# Audio_Spektrum_Analyser.net
KiCad netlist of a schematic drawn in EAGLE
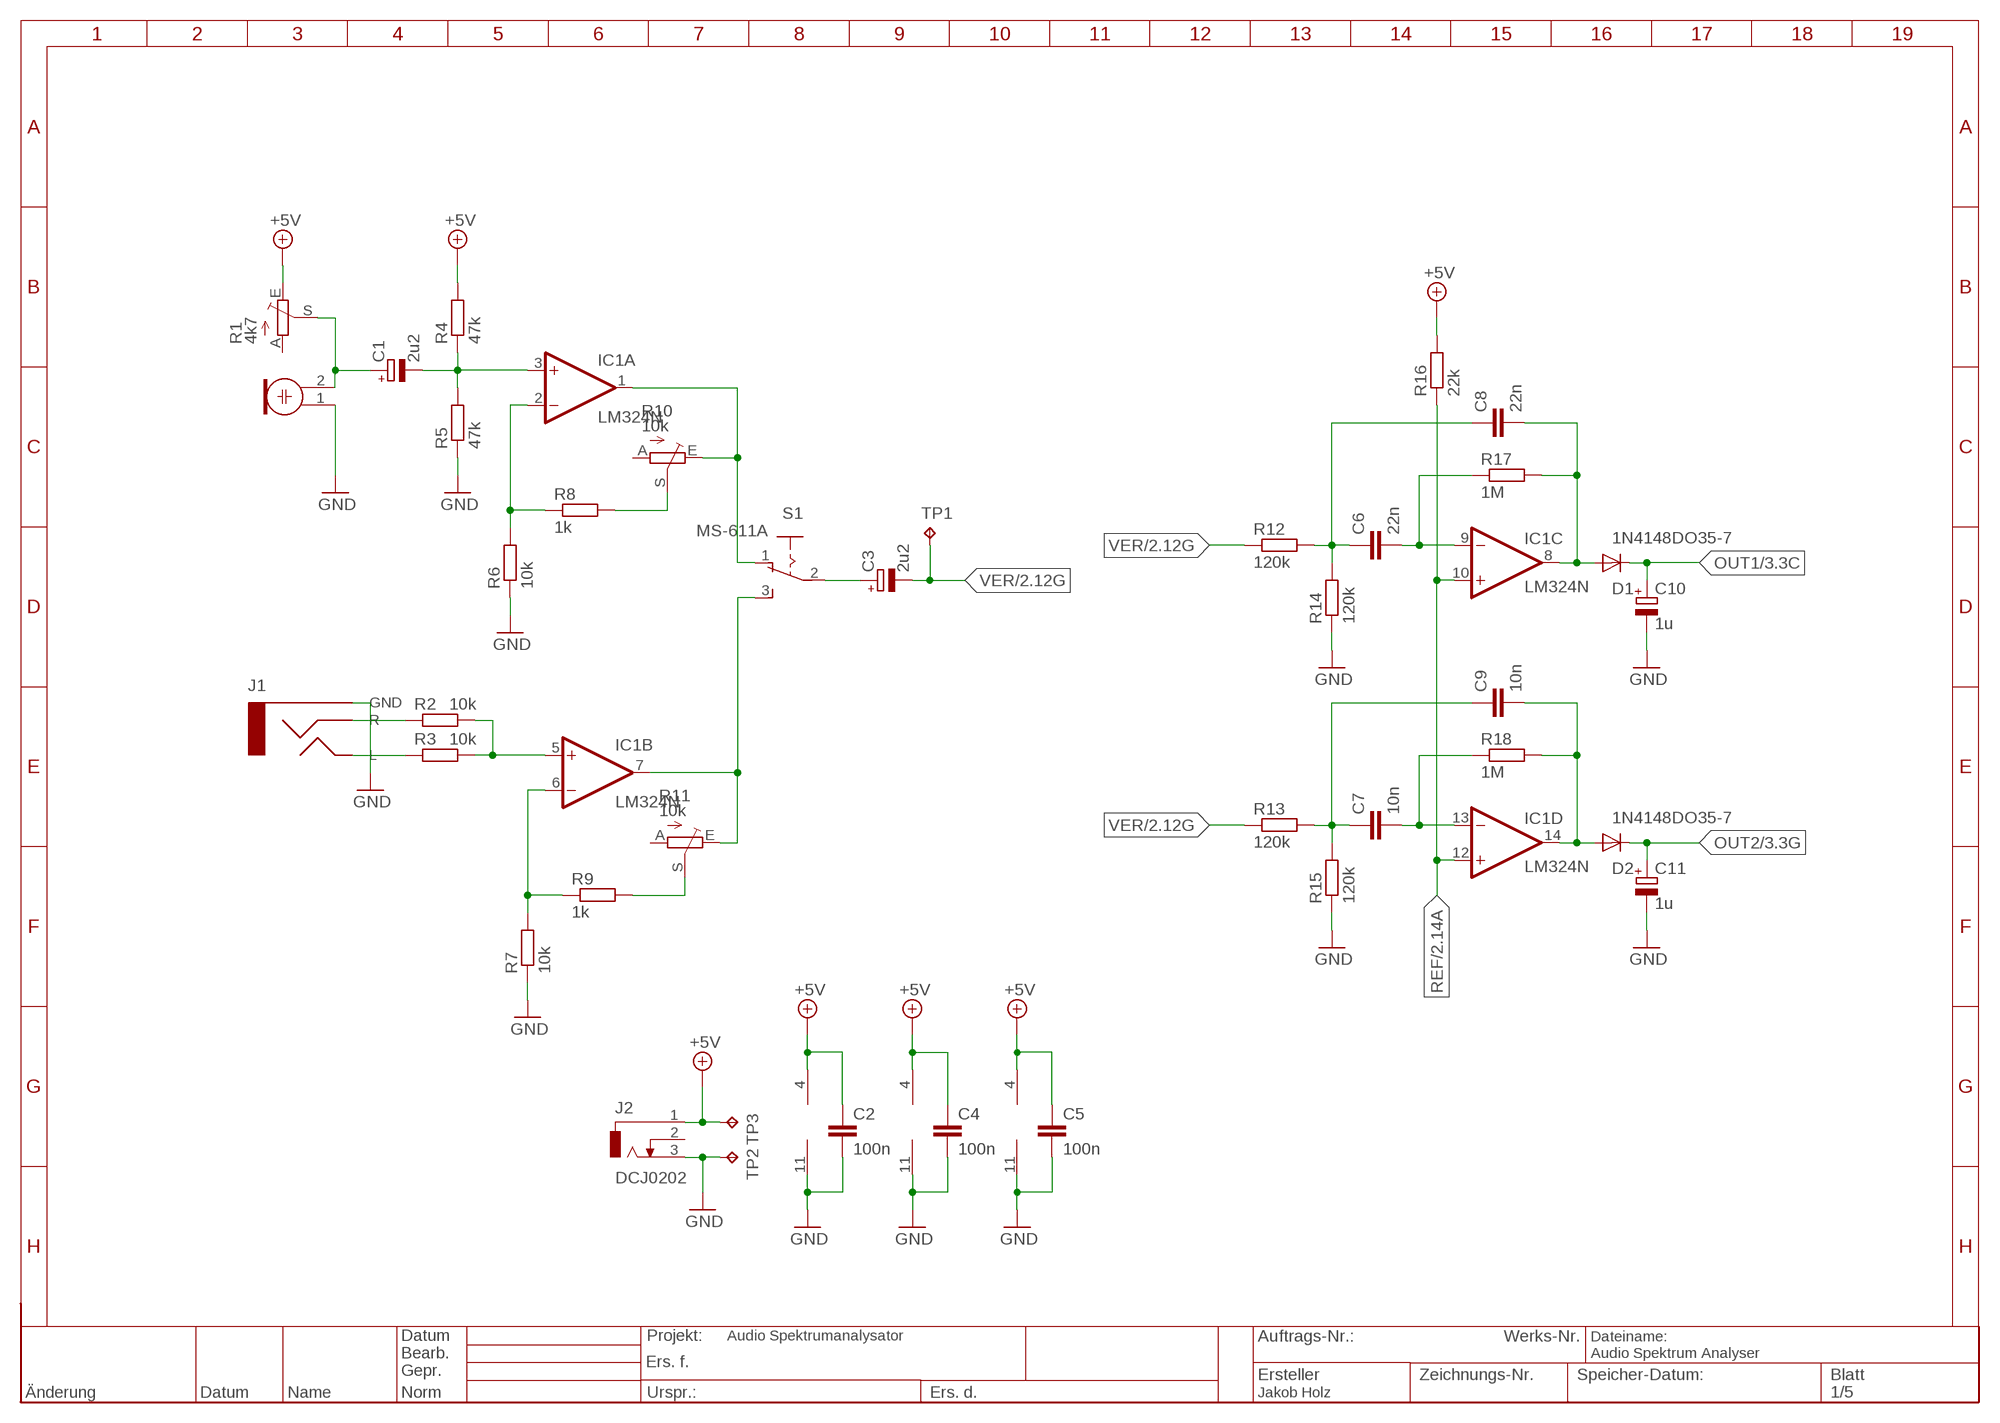
[diagram p0: schematic, sheet 1]
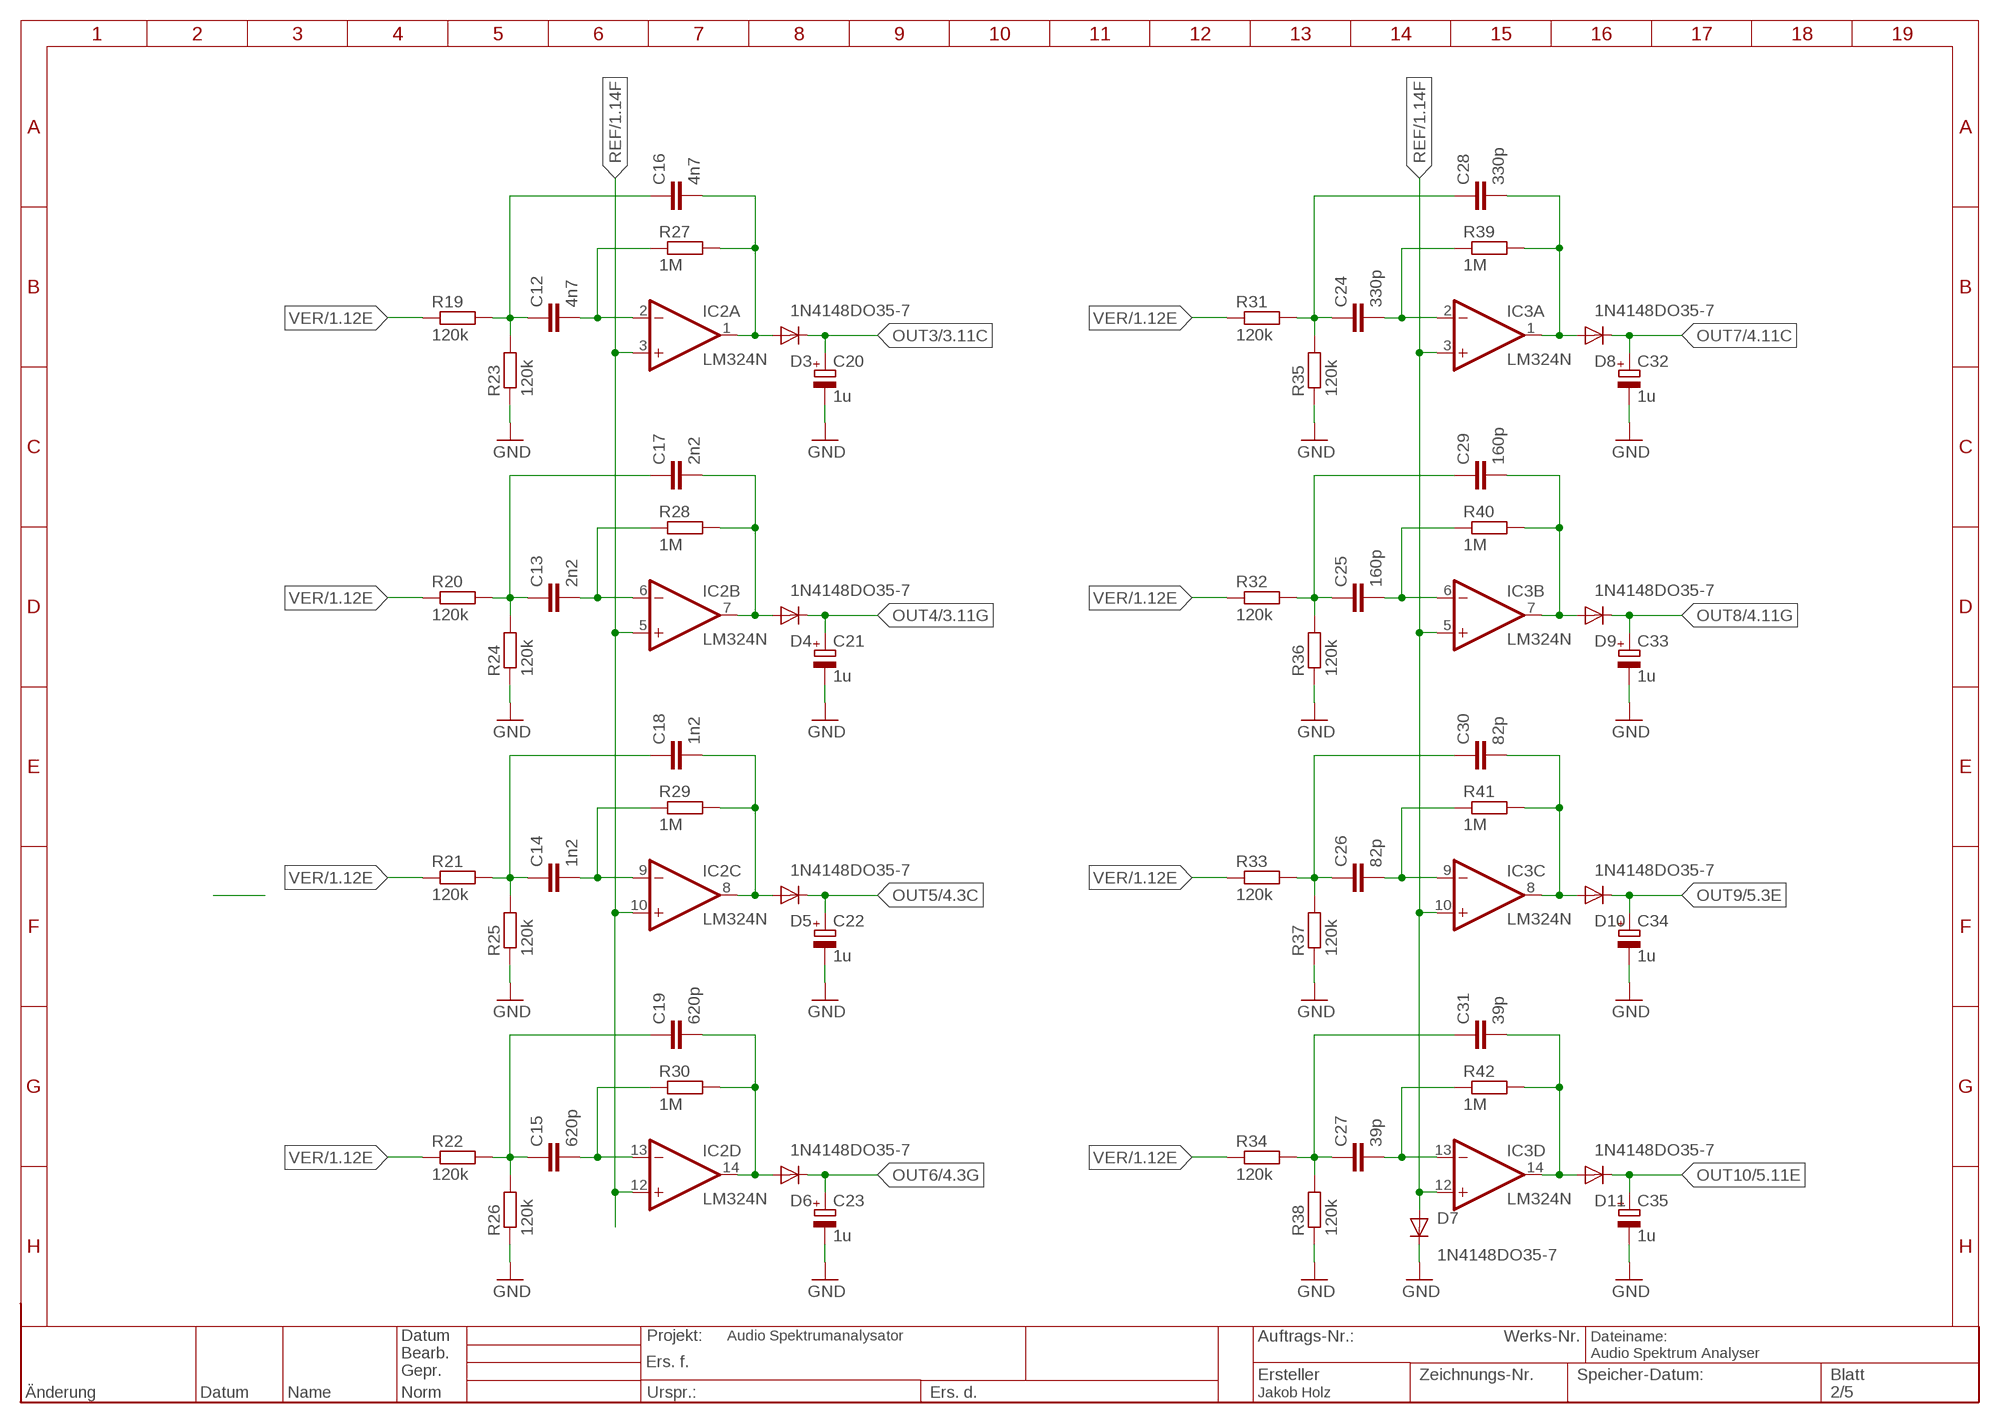
[diagram p1: schematic, sheet 2]
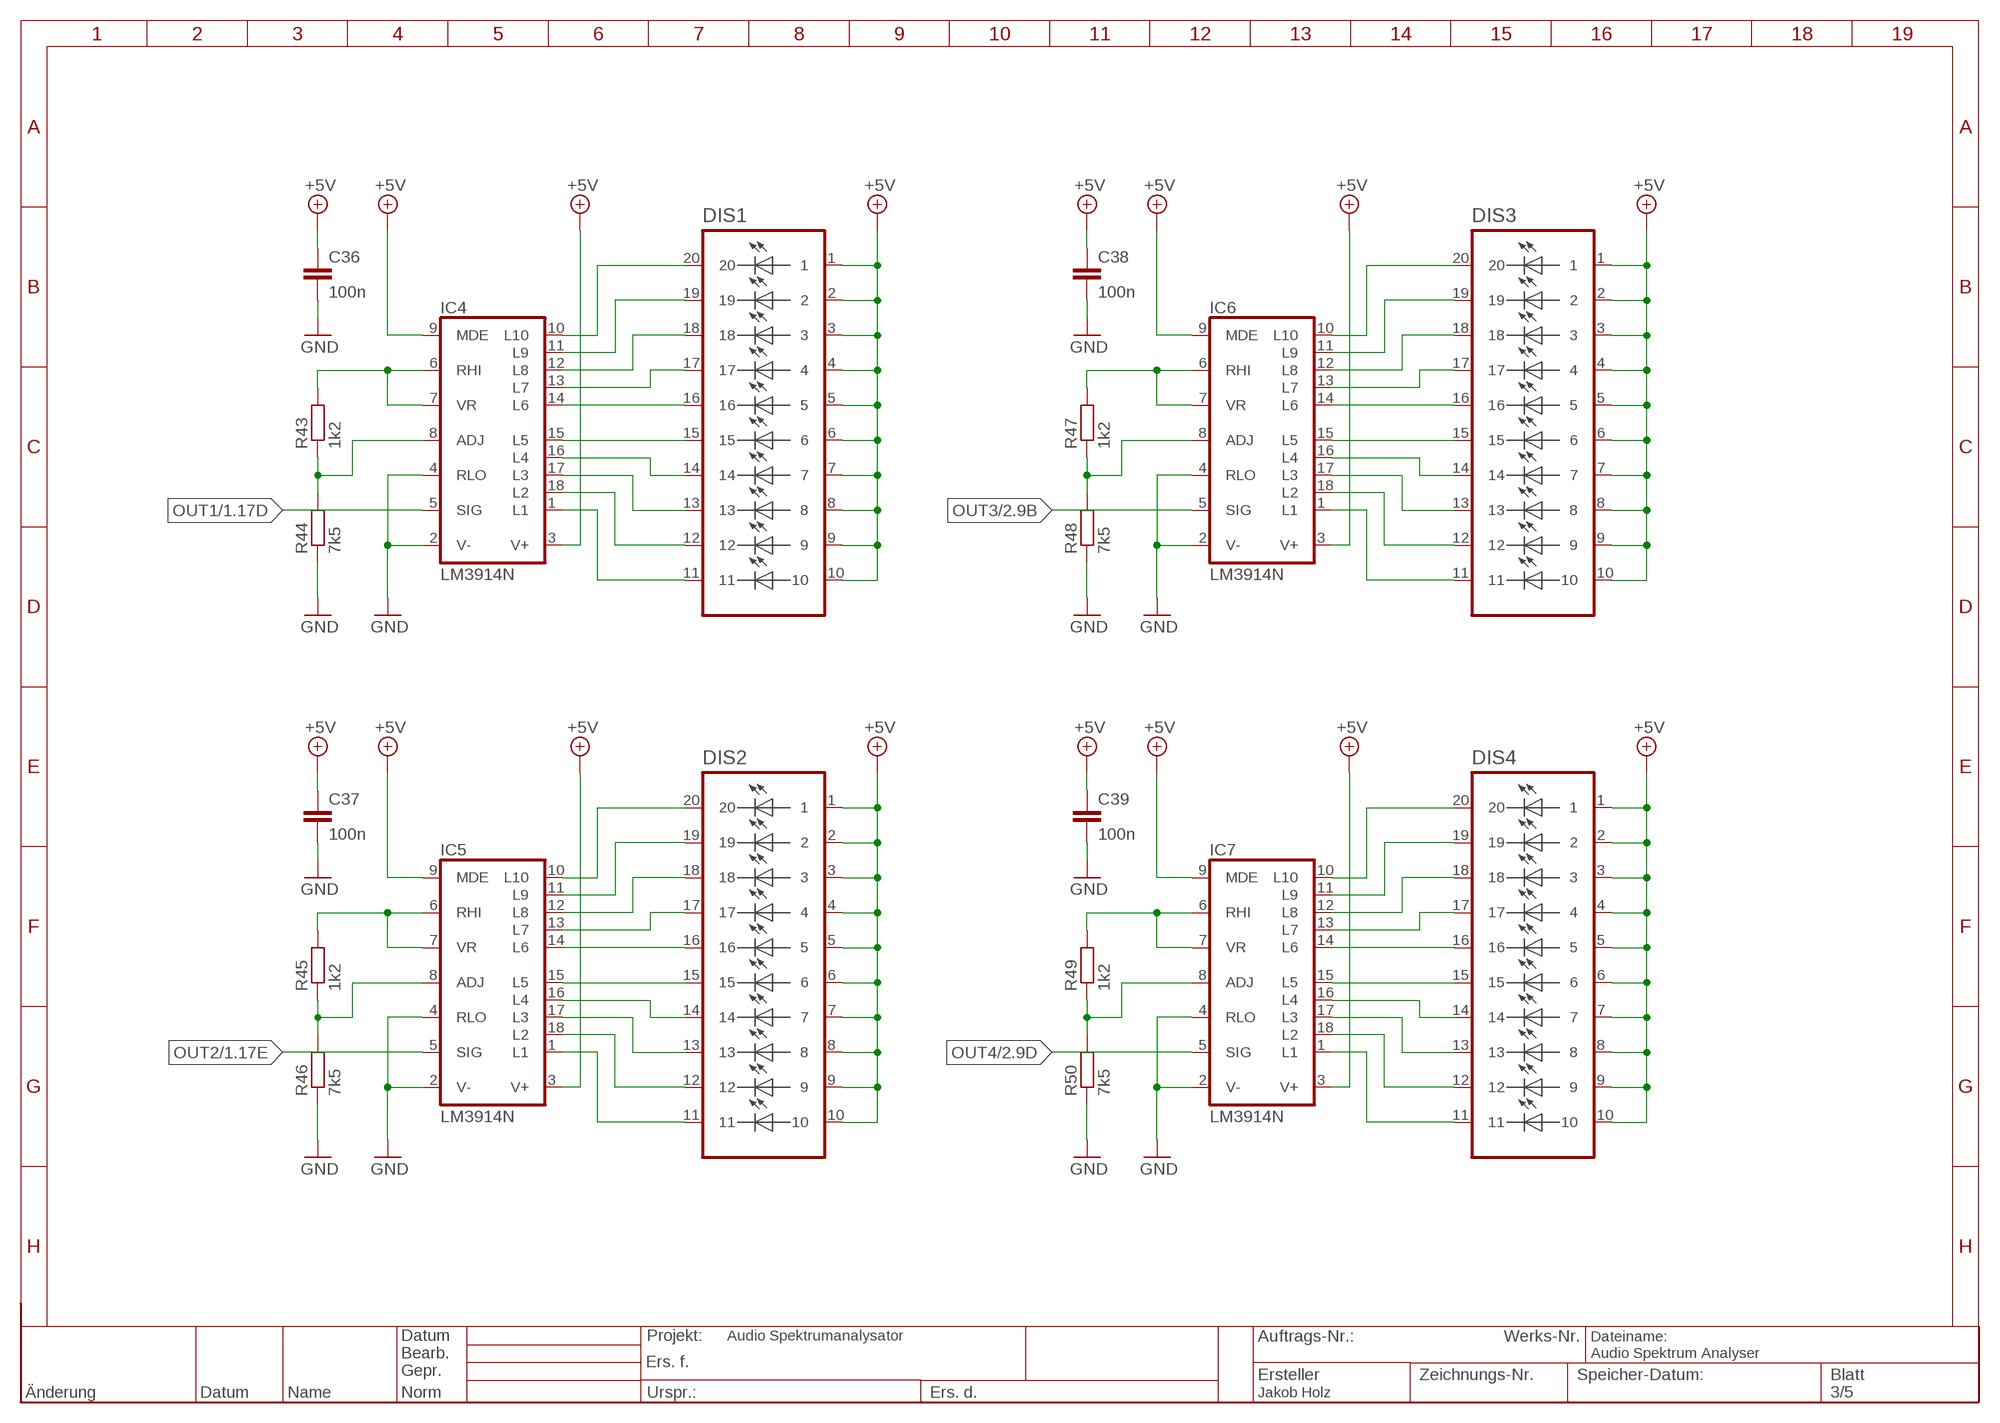
[diagram p2: schematic, sheet 3]
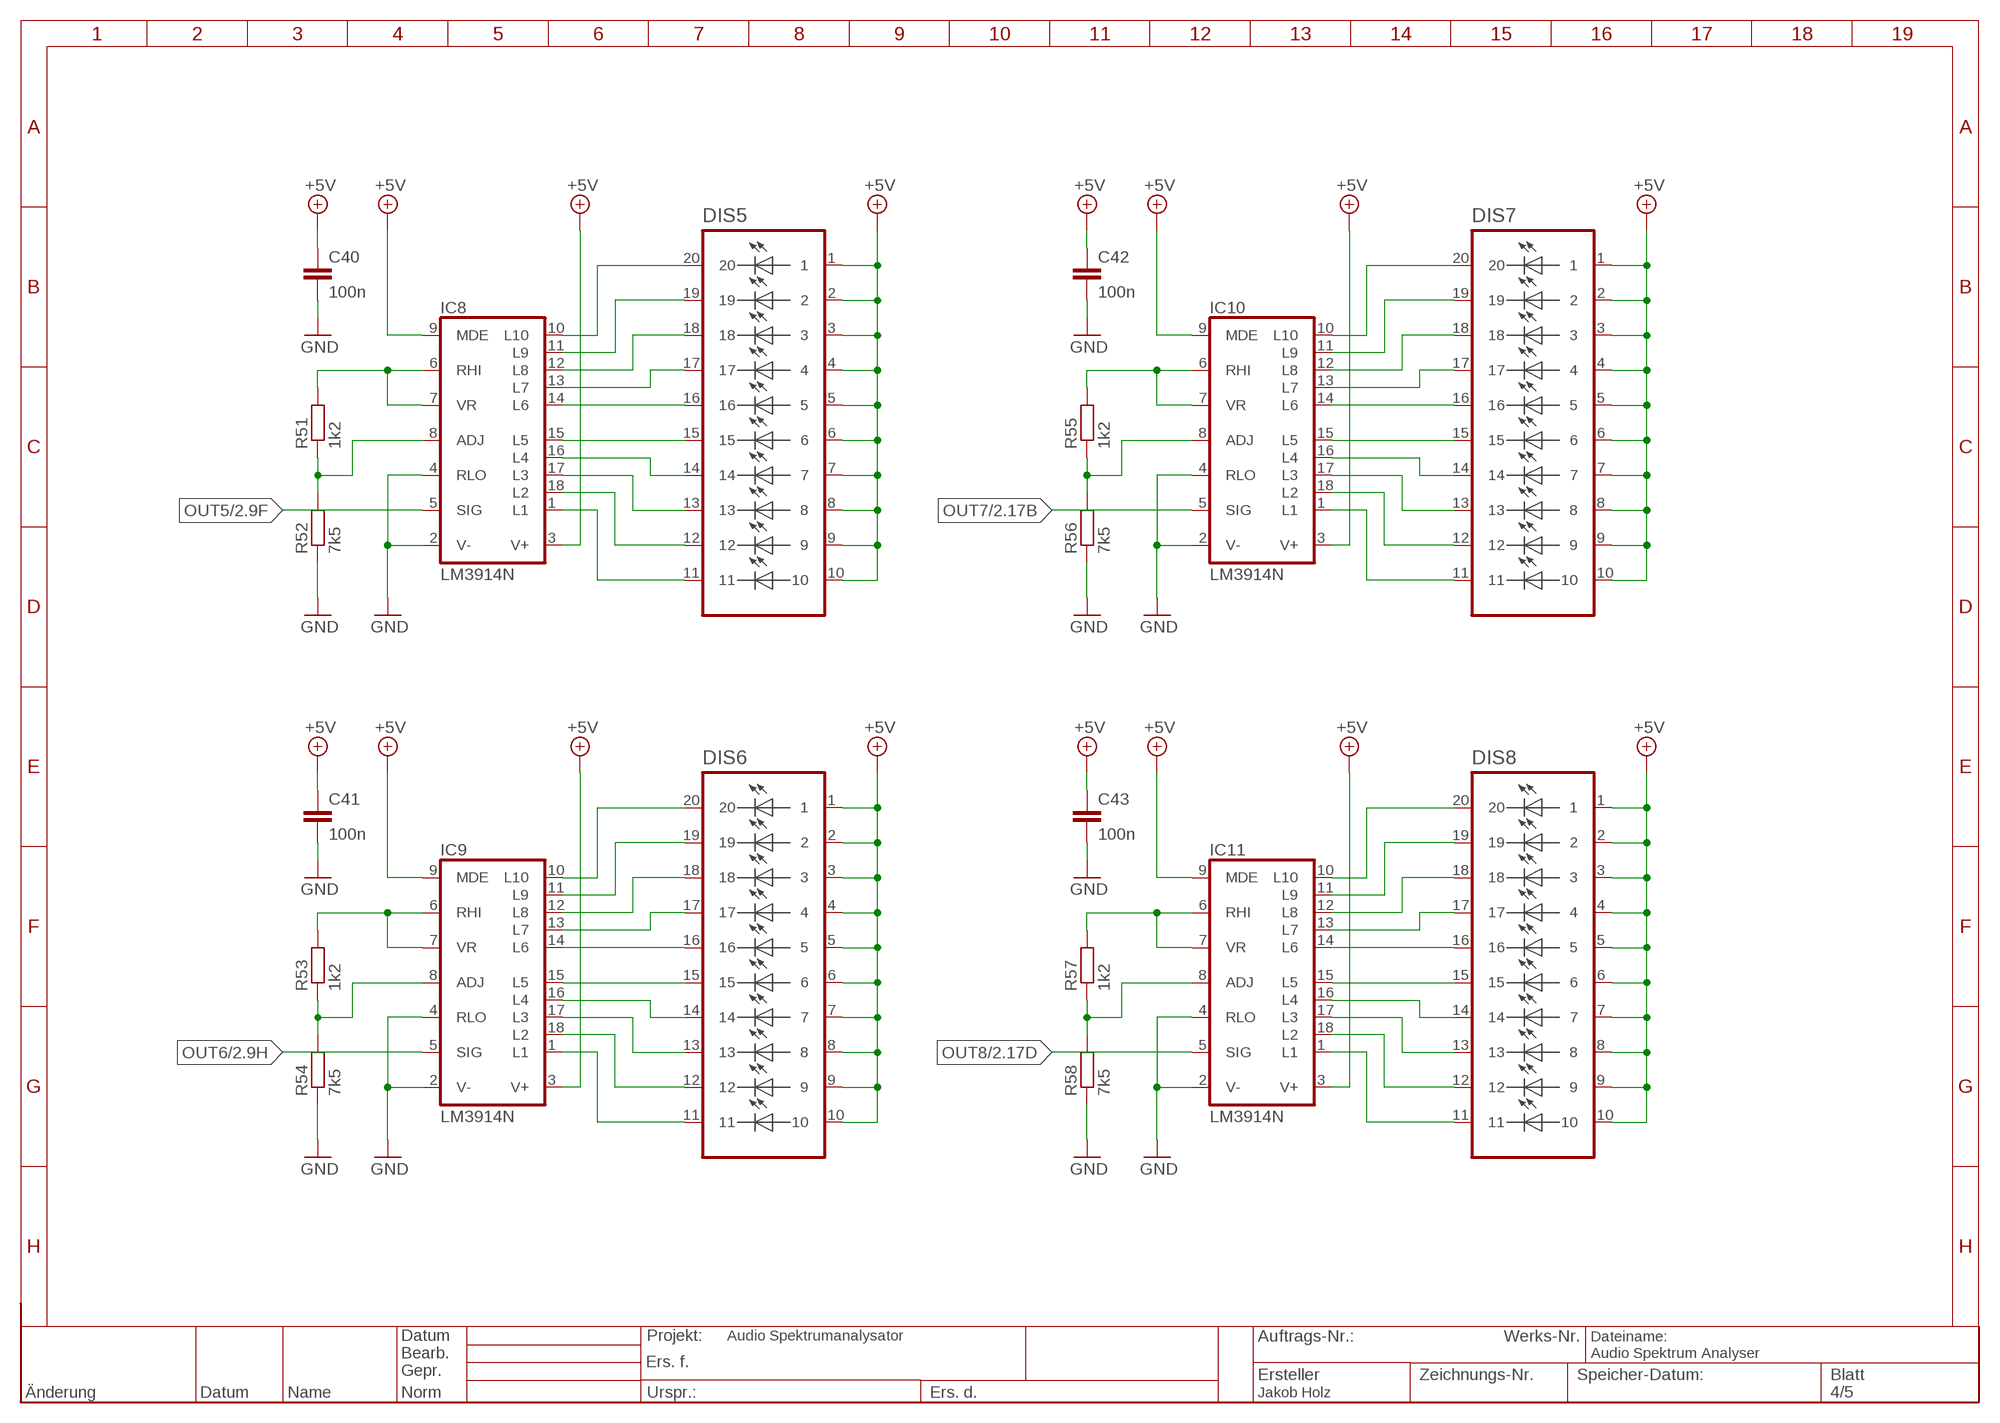
[diagram p3: schematic, sheet 4]
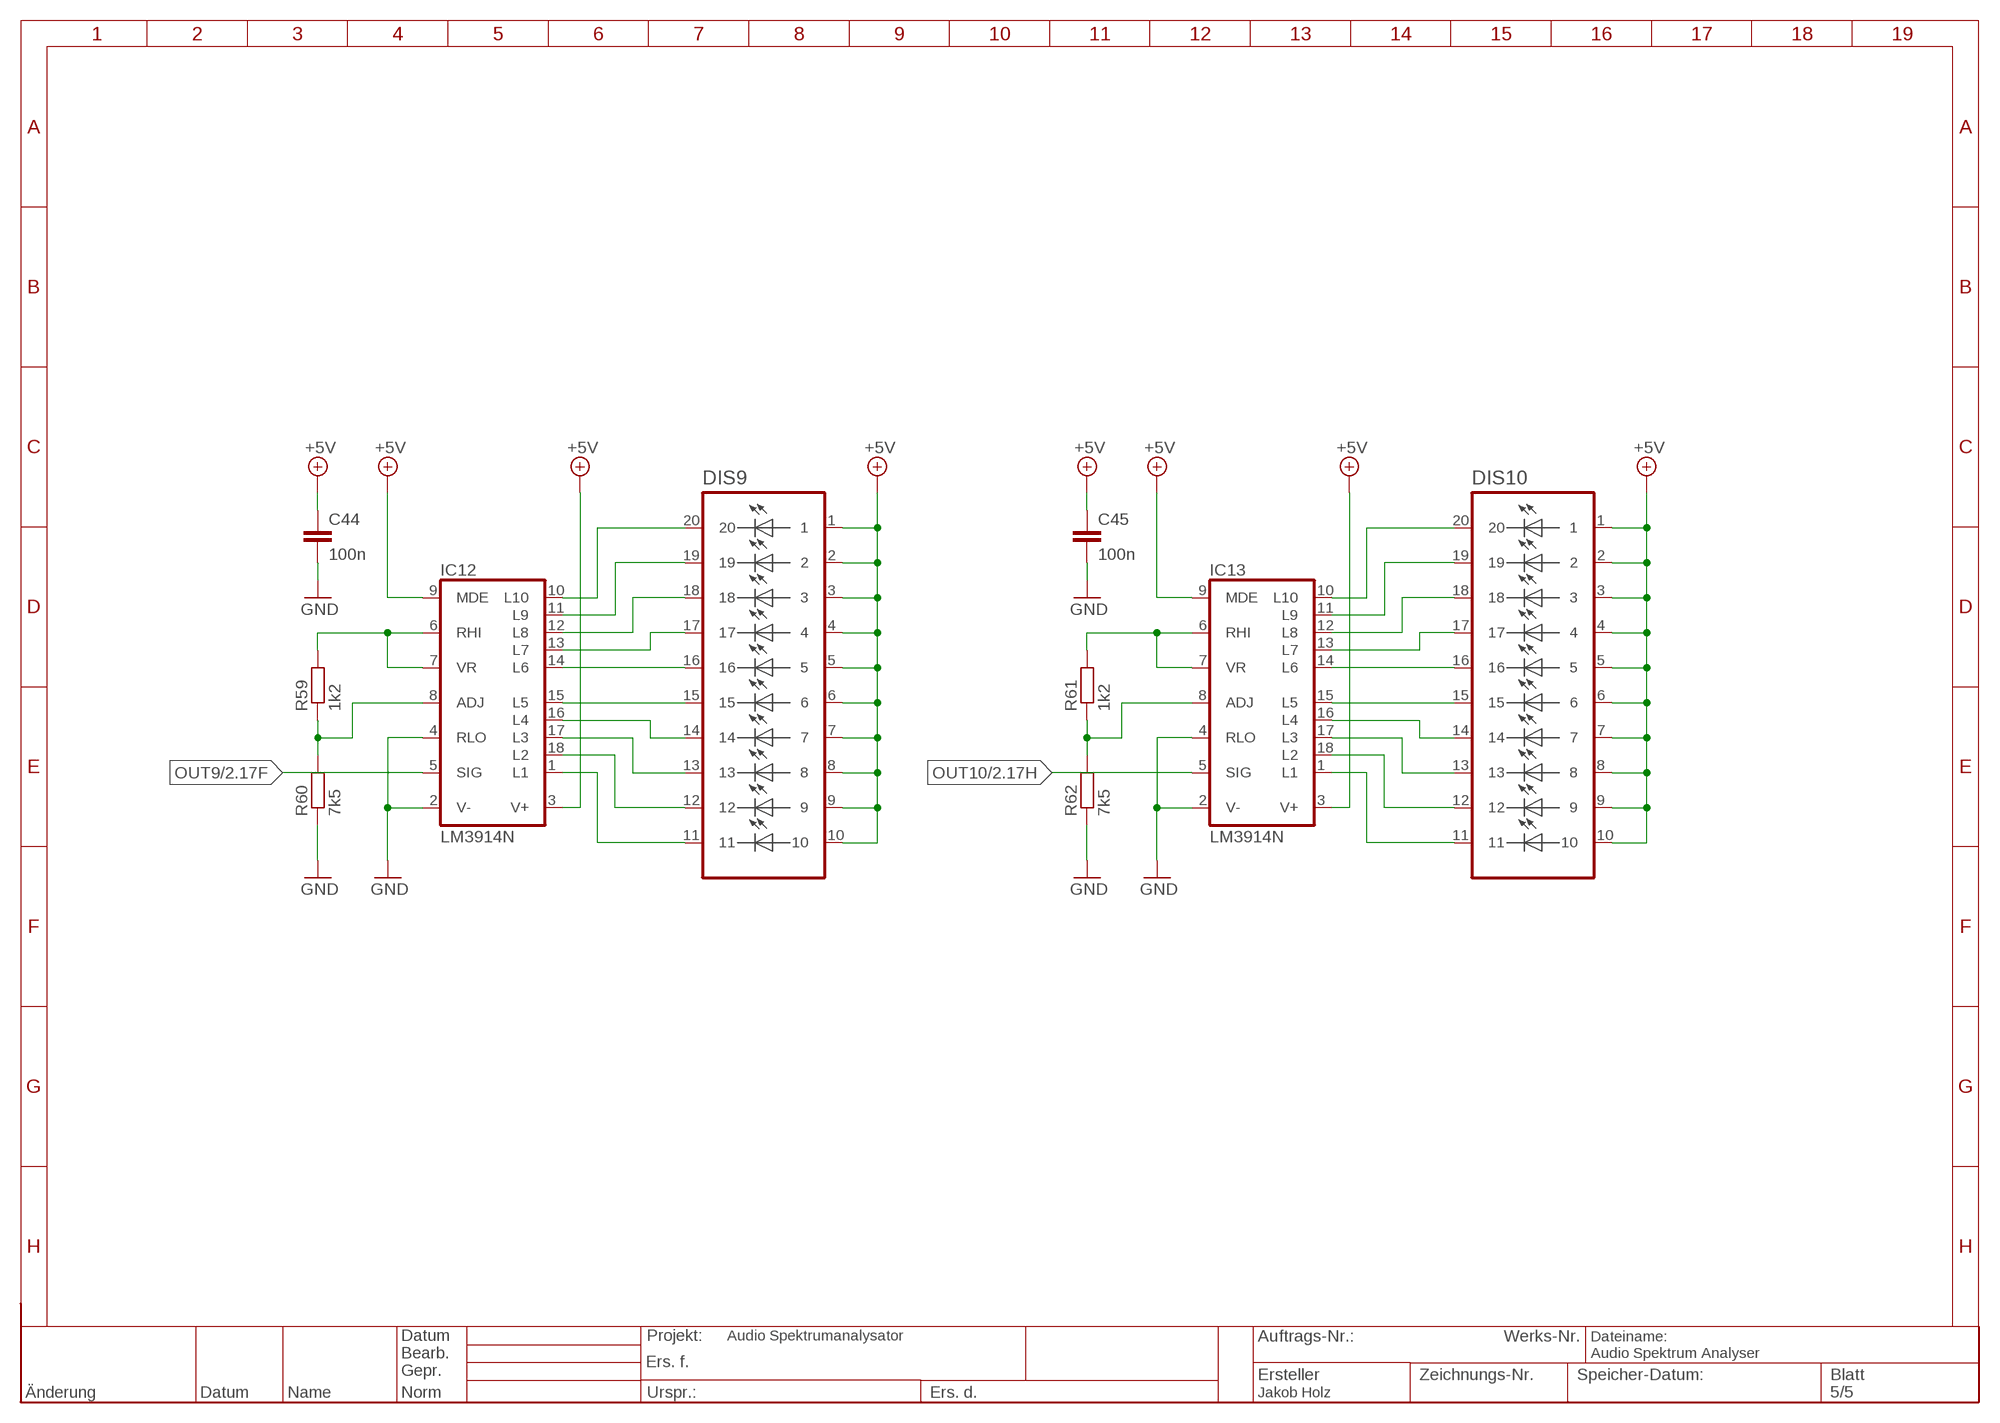
[diagram p4: schematic, sheet 5]

(export (version "E")
  (design (tool "Eeschema 10.0.6"))
  (components
    (comp (ref "C44")
      (value "100n")
      (footprint "eagle-import:C050-024X044")
      (libsource (lib "eagle-import") (part "C-EU050-024X044"))
    )
    (comp (ref "C45")
      (value "100n")
      (footprint "eagle-import:C050-024X044")
      (libsource (lib "eagle-import") (part "C-EU050-024X044"))
    )
    (comp (ref "DIS9")
      (value "SHB10R")
      (footprint "eagle-import:SHB10R")
      (libsource (lib "eagle-import") (part "SHB10R"))
    )
    (comp (ref "DIS10")
      (value "SHB10R")
      (footprint "eagle-import:SHB10R")
      (libsource (lib "eagle-import") (part "SHB10R"))
    )
    (comp (ref "IC12")
      (value "LM3914N")
      (footprint "eagle-import:DIL18")
      (libsource (lib "eagle-import") (part "LM3914N"))
    )
    (comp (ref "IC13")
      (value "LM3914N")
      (footprint "eagle-import:DIL18")
      (libsource (lib "eagle-import") (part "LM3914N"))
    )
    (comp (ref "R59")
      (value "1k2")
      (footprint "eagle-import:0207_7")
      (libsource (lib "eagle-import") (part "resistor_348_R-EU_0207/7"))
    )
    (comp (ref "R60")
      (value "7k5")
      (footprint "eagle-import:0207_7")
      (libsource (lib "eagle-import") (part "resistor_348_R-EU_0207/7"))
    )
    (comp (ref "R61")
      (value "1k2")
      (footprint "eagle-import:0207_7")
      (libsource (lib "eagle-import") (part "resistor_348_R-EU_0207/7"))
    )
    (comp (ref "R62")
      (value "7k5")
      (footprint "eagle-import:0207_7")
      (libsource (lib "eagle-import") (part "resistor_348_R-EU_0207/7"))
    )
    (comp (ref "C1")
      (value "2u2")
      (footprint "eagle-import:E2,5-5")
      (libsource (lib "eagle-import") (part "CPOL-EUE2.5-5"))
    )
    (comp (ref "C2")
      (value "100n")
      (footprint "eagle-import:C050-024X044")
      (libsource (lib "eagle-import") (part "C-EU050-024X044"))
    )
    (comp (ref "C3")
      (value "2u2")
      (footprint "eagle-import:E2,5-5")
      (libsource (lib "eagle-import") (part "CPOL-EUE2.5-5"))
    )
    (comp (ref "C4")
      (value "100n")
      (footprint "eagle-import:C050-024X044")
      (libsource (lib "eagle-import") (part "C-EU050-024X044"))
    )
    (comp (ref "C5")
      (value "100n")
      (footprint "eagle-import:C050-024X044")
      (libsource (lib "eagle-import") (part "C-EU050-024X044"))
    )
    (comp (ref "C6")
      (value "22n")
      (footprint "eagle-import:C025-024X044")
      (libsource (lib "eagle-import") (part "C-EU025-024X044"))
    )
    (comp (ref "C7")
      (value "10n")
      (footprint "eagle-import:C025-024X044")
      (libsource (lib "eagle-import") (part "C-EU025-024X044"))
    )
    (comp (ref "C8")
      (value "22n")
      (footprint "eagle-import:C025-024X044")
      (libsource (lib "eagle-import") (part "C-EU025-024X044"))
    )
    (comp (ref "C9")
      (value "10n")
      (footprint "eagle-import:C025-024X044")
      (libsource (lib "eagle-import") (part "C-EU025-024X044"))
    )
    (comp (ref "C10")
      (value "1u")
      (footprint "eagle-import:E2,5-5")
      (libsource (lib "eagle-import") (part "CPOL-EUE2.5-5"))
    )
    (comp (ref "C11")
      (value "1u")
      (footprint "eagle-import:E2,5-5")
      (libsource (lib "eagle-import") (part "CPOL-EUE2.5-5"))
    )
    (comp (ref "D1")
      (value "1N4148DO35-7")
      (footprint "eagle-import:DO35-7")
      (libsource (lib "eagle-import") (part "1N4148DO35-7"))
    )
    (comp (ref "D2")
      (value "1N4148DO35-7")
      (footprint "eagle-import:DO35-7")
      (libsource (lib "eagle-import") (part "1N4148DO35-7"))
    )
    (comp (ref "IC1")
      (value "LM324N")
      (footprint "eagle-import:DIL14")
      (libsource (lib "eagle-import") (part "LM324N"))
    )
    (comp (ref "IC2")
      (value "LM324N")
      (footprint "eagle-import:DIL14")
      (libsource (lib "eagle-import") (part "LM324N"))
    )
    (comp (ref "IC3")
      (value "LM324N")
      (footprint "eagle-import:DIL14")
      (libsource (lib "eagle-import") (part "LM324N"))
    )
    (comp (ref "J1")
      (value "2.5MM-AUXPC")
      (footprint "eagle-import:2.5MM-AUX_PC")
      (libsource (lib "eagle-import") (part "2.5MM-AUXPC"))
    )
    (comp (ref "J2")
      (value "DCJ0202")
      (footprint "eagle-import:DCJ0202")
      (libsource (lib "eagle-import") (part "DCJ0202"))
    )
    (comp (ref "M1")
      (value "ELECTRET_MICROPHON-F6050AP")
      (footprint "eagle-import:F6050AP")
      (libsource (lib "eagle-import") (part "ELECTRET_MICROPHON-F6050AP"))
    )
    (comp (ref "R1")
      (value "4k7")
      (footprint "eagle-import:CA6V")
      (libsource (lib "eagle-import") (part "TRIM_EU-CA6V"))
    )
    (comp (ref "R2")
      (value "10k")
      (footprint "eagle-import:0207_7")
      (libsource (lib "eagle-import") (part "R-EU_0207/7"))
    )
    (comp (ref "R3")
      (value "10k")
      (footprint "eagle-import:0207_7")
      (libsource (lib "eagle-import") (part "R-EU_0207/7"))
    )
    (comp (ref "R4")
      (value "47k")
      (footprint "eagle-import:0207_7")
      (libsource (lib "eagle-import") (part "R-EU_0207/7"))
    )
    (comp (ref "R5")
      (value "47k")
      (footprint "eagle-import:0207_7")
      (libsource (lib "eagle-import") (part "R-EU_0207/7"))
    )
    (comp (ref "R6")
      (value "10k")
      (footprint "eagle-import:0207_7")
      (libsource (lib "eagle-import") (part "R-EU_0207/7"))
    )
    (comp (ref "R7")
      (value "10k")
      (footprint "eagle-import:0207_7")
      (libsource (lib "eagle-import") (part "resistor_348_R-EU_0207/7"))
    )
    (comp (ref "R8")
      (value "1k")
      (footprint "eagle-import:0207_7")
      (libsource (lib "eagle-import") (part "R-EU_0207/7"))
    )
    (comp (ref "R9")
      (value "1k")
      (footprint "eagle-import:0207_7")
      (libsource (lib "eagle-import") (part "resistor_348_R-EU_0207/7"))
    )
    (comp (ref "R10")
      (value "10k")
      (footprint "eagle-import:CA6V")
      (libsource (lib "eagle-import") (part "TRIM_EU-CA6V"))
    )
    (comp (ref "R11")
      (value "10k")
      (footprint "eagle-import:CA6V")
      (libsource (lib "eagle-import") (part "TRIM_EU-CA6V"))
    )
    (comp (ref "R12")
      (value "120k")
      (footprint "eagle-import:0207_7")
      (libsource (lib "eagle-import") (part "resistor_348_R-EU_0207/7"))
    )
    (comp (ref "R13")
      (value "120k")
      (footprint "eagle-import:0207_7")
      (libsource (lib "eagle-import") (part "resistor_348_R-EU_0207/7"))
    )
    (comp (ref "R14")
      (value "120k")
      (footprint "eagle-import:0207_7")
      (libsource (lib "eagle-import") (part "resistor_348_R-EU_0207/7"))
    )
    (comp (ref "R15")
      (value "120k")
      (footprint "eagle-import:0207_7")
      (libsource (lib "eagle-import") (part "resistor_348_R-EU_0207/7"))
    )
    (comp (ref "R16")
      (value "22k")
      (footprint "eagle-import:0207_7")
      (libsource (lib "eagle-import") (part "resistor_348_R-EU_0207/7"))
    )
    (comp (ref "R17")
      (value "1M")
      (footprint "eagle-import:0207_7")
      (libsource (lib "eagle-import") (part "resistor_348_R-EU_0207/7"))
    )
    (comp (ref "R18")
      (value "1M")
      (footprint "eagle-import:0207_7")
      (libsource (lib "eagle-import") (part "resistor_348_R-EU_0207/7"))
    )
    (comp (ref "S1")
      (value "MS-611A")
      (footprint "eagle-import:MS-611A")
      (libsource (lib "eagle-import") (part "MS-611A"))
    )
    (comp (ref "TP1")
      (value "TPPAD1-20")
      (footprint "eagle-import:P1-20")
      (libsource (lib "eagle-import") (part "TPPAD1-20"))
    )
    (comp (ref "TP2")
      (value "TPPAD1-20")
      (footprint "eagle-import:P1-20")
      (libsource (lib "eagle-import") (part "TPPAD1-20"))
    )
    (comp (ref "TP3")
      (value "TPPAD1-20")
      (footprint "eagle-import:P1-20")
      (libsource (lib "eagle-import") (part "TPPAD1-20"))
    )
    (comp (ref "C36")
      (value "100n")
      (footprint "eagle-import:C050-024X044")
      (libsource (lib "eagle-import") (part "C-EU050-024X044"))
    )
    (comp (ref "C37")
      (value "100n")
      (footprint "eagle-import:C050-024X044")
      (libsource (lib "eagle-import") (part "C-EU050-024X044"))
    )
    (comp (ref "C38")
      (value "100n")
      (footprint "eagle-import:C050-024X044")
      (libsource (lib "eagle-import") (part "C-EU050-024X044"))
    )
    (comp (ref "C39")
      (value "100n")
      (footprint "eagle-import:C050-024X044")
      (libsource (lib "eagle-import") (part "C-EU050-024X044"))
    )
    (comp (ref "DIS1")
      (value "SHB10R")
      (footprint "eagle-import:SHB10R")
      (libsource (lib "eagle-import") (part "SHB10R"))
    )
    (comp (ref "DIS2")
      (value "SHB10R")
      (footprint "eagle-import:SHB10R")
      (libsource (lib "eagle-import") (part "SHB10R"))
    )
    (comp (ref "DIS3")
      (value "SHB10R")
      (footprint "eagle-import:SHB10R")
      (libsource (lib "eagle-import") (part "SHB10R"))
    )
    (comp (ref "DIS4")
      (value "SHB10R")
      (footprint "eagle-import:SHB10R")
      (libsource (lib "eagle-import") (part "SHB10R"))
    )
    (comp (ref "IC4")
      (value "LM3914N")
      (footprint "eagle-import:DIL18")
      (libsource (lib "eagle-import") (part "LM3914N"))
    )
    (comp (ref "IC5")
      (value "LM3914N")
      (footprint "eagle-import:DIL18")
      (libsource (lib "eagle-import") (part "LM3914N"))
    )
    (comp (ref "IC6")
      (value "LM3914N")
      (footprint "eagle-import:DIL18")
      (libsource (lib "eagle-import") (part "LM3914N"))
    )
    (comp (ref "IC7")
      (value "LM3914N")
      (footprint "eagle-import:DIL18")
      (libsource (lib "eagle-import") (part "LM3914N"))
    )
    (comp (ref "R43")
      (value "1k2")
      (footprint "eagle-import:0207_7")
      (libsource (lib "eagle-import") (part "resistor_348_R-EU_0207/7"))
    )
    (comp (ref "R44")
      (value "7k5")
      (footprint "eagle-import:0207_7")
      (libsource (lib "eagle-import") (part "resistor_348_R-EU_0207/7"))
    )
    (comp (ref "R45")
      (value "1k2")
      (footprint "eagle-import:0207_7")
      (libsource (lib "eagle-import") (part "resistor_348_R-EU_0207/7"))
    )
    (comp (ref "R46")
      (value "7k5")
      (footprint "eagle-import:0207_7")
      (libsource (lib "eagle-import") (part "resistor_348_R-EU_0207/7"))
    )
    (comp (ref "R47")
      (value "1k2")
      (footprint "eagle-import:0207_7")
      (libsource (lib "eagle-import") (part "resistor_348_R-EU_0207/7"))
    )
    (comp (ref "R48")
      (value "7k5")
      (footprint "eagle-import:0207_7")
      (libsource (lib "eagle-import") (part "resistor_348_R-EU_0207/7"))
    )
    (comp (ref "R49")
      (value "1k2")
      (footprint "eagle-import:0207_7")
      (libsource (lib "eagle-import") (part "resistor_348_R-EU_0207/7"))
    )
    (comp (ref "R50")
      (value "7k5")
      (footprint "eagle-import:0207_7")
      (libsource (lib "eagle-import") (part "resistor_348_R-EU_0207/7"))
    )
    (comp (ref "C12")
      (value "4n7")
      (footprint "eagle-import:C025-024X044")
      (libsource (lib "eagle-import") (part "C-EU025-024X044"))
    )
    (comp (ref "C13")
      (value "2n2")
      (footprint "eagle-import:C025-024X044")
      (libsource (lib "eagle-import") (part "C-EU025-024X044"))
    )
    (comp (ref "C14")
      (value "1n2")
      (footprint "eagle-import:C025-024X044")
      (libsource (lib "eagle-import") (part "C-EU025-024X044"))
    )
    (comp (ref "C15")
      (value "620p")
      (footprint "eagle-import:C025-024X044")
      (libsource (lib "eagle-import") (part "C-EU025-024X044"))
    )
    (comp (ref "C16")
      (value "4n7")
      (footprint "eagle-import:C025-024X044")
      (libsource (lib "eagle-import") (part "C-EU025-024X044"))
    )
    (comp (ref "C17")
      (value "2n2")
      (footprint "eagle-import:C025-024X044")
      (libsource (lib "eagle-import") (part "C-EU025-024X044"))
    )
    (comp (ref "C18")
      (value "1n2")
      (footprint "eagle-import:C025-024X044")
      (libsource (lib "eagle-import") (part "C-EU025-024X044"))
    )
    (comp (ref "C19")
      (value "620p")
      (footprint "eagle-import:C025-024X044")
      (libsource (lib "eagle-import") (part "C-EU025-024X044"))
    )
    (comp (ref "C20")
      (value "1u")
      (footprint "eagle-import:E2,5-5")
      (libsource (lib "eagle-import") (part "CPOL-EUE2.5-5"))
    )
    (comp (ref "C21")
      (value "1u")
      (footprint "eagle-import:E2,5-5")
      (libsource (lib "eagle-import") (part "CPOL-EUE2.5-5"))
    )
    (comp (ref "C22")
      (value "1u")
      (footprint "eagle-import:E2,5-5")
      (libsource (lib "eagle-import") (part "CPOL-EUE2.5-5"))
    )
    (comp (ref "C23")
      (value "1u")
      (footprint "eagle-import:E2,5-5")
      (libsource (lib "eagle-import") (part "CPOL-EUE2.5-5"))
    )
    (comp (ref "C24")
      (value "330p")
      (footprint "eagle-import:C025-024X044")
      (libsource (lib "eagle-import") (part "C-EU025-024X044"))
    )
    (comp (ref "C25")
      (value "160p")
      (footprint "eagle-import:C025-024X044")
      (libsource (lib "eagle-import") (part "C-EU025-024X044"))
    )
    (comp (ref "C26")
      (value "82p")
      (footprint "eagle-import:C025-024X044")
      (libsource (lib "eagle-import") (part "C-EU025-024X044"))
    )
    (comp (ref "C27")
      (value "39p")
      (footprint "eagle-import:C025-024X044")
      (libsource (lib "eagle-import") (part "C-EU025-024X044"))
    )
    (comp (ref "C28")
      (value "330p")
      (footprint "eagle-import:C025-024X044")
      (libsource (lib "eagle-import") (part "C-EU025-024X044"))
    )
    (comp (ref "C29")
      (value "160p")
      (footprint "eagle-import:C025-024X044")
      (libsource (lib "eagle-import") (part "C-EU025-024X044"))
    )
    (comp (ref "C30")
      (value "82p")
      (footprint "eagle-import:C025-024X044")
      (libsource (lib "eagle-import") (part "C-EU025-024X044"))
    )
    (comp (ref "C31")
      (value "39p")
      (footprint "eagle-import:C025-024X044")
      (libsource (lib "eagle-import") (part "C-EU025-024X044"))
    )
    (comp (ref "C32")
      (value "1u")
      (footprint "eagle-import:E2,5-5")
      (libsource (lib "eagle-import") (part "CPOL-EUE2.5-5"))
    )
    (comp (ref "C33")
      (value "1u")
      (footprint "eagle-import:E2,5-5")
      (libsource (lib "eagle-import") (part "CPOL-EUE2.5-5"))
    )
    (comp (ref "C34")
      (value "1u")
      (footprint "eagle-import:E2,5-5")
      (libsource (lib "eagle-import") (part "CPOL-EUE2.5-5"))
    )
    (comp (ref "C35")
      (value "1u")
      (footprint "eagle-import:E2,5-5")
      (libsource (lib "eagle-import") (part "CPOL-EUE2.5-5"))
    )
    (comp (ref "D3")
      (value "1N4148DO35-7")
      (footprint "eagle-import:DO35-7")
      (libsource (lib "eagle-import") (part "1N4148DO35-7"))
    )
    (comp (ref "D4")
      (value "1N4148DO35-7")
      (footprint "eagle-import:DO35-7")
      (libsource (lib "eagle-import") (part "1N4148DO35-7"))
    )
    (comp (ref "D5")
      (value "1N4148DO35-7")
      (footprint "eagle-import:DO35-7")
      (libsource (lib "eagle-import") (part "1N4148DO35-7"))
    )
    (comp (ref "D6")
      (value "1N4148DO35-7")
      (footprint "eagle-import:DO35-7")
      (libsource (lib "eagle-import") (part "1N4148DO35-7"))
    )
    (comp (ref "D7")
      (value "1N4148DO35-7")
      (footprint "eagle-import:DO35-7")
      (libsource (lib "eagle-import") (part "1N4148DO35-7"))
    )
    (comp (ref "D8")
      (value "1N4148DO35-7")
      (footprint "eagle-import:DO35-7")
      (libsource (lib "eagle-import") (part "1N4148DO35-7"))
    )
    (comp (ref "D9")
      (value "1N4148DO35-7")
      (footprint "eagle-import:DO35-7")
      (libsource (lib "eagle-import") (part "1N4148DO35-7"))
    )
    (comp (ref "D10")
      (value "1N4148DO35-7")
      (footprint "eagle-import:DO35-7")
      (libsource (lib "eagle-import") (part "1N4148DO35-7"))
    )
    (comp (ref "D11")
      (value "1N4148DO35-7")
      (footprint "eagle-import:DO35-7")
      (libsource (lib "eagle-import") (part "1N4148DO35-7"))
    )
    (comp (ref "R19")
      (value "120k")
      (footprint "eagle-import:0207_7")
      (libsource (lib "eagle-import") (part "resistor_348_R-EU_0207/7"))
    )
    (comp (ref "R20")
      (value "120k")
      (footprint "eagle-import:0207_7")
      (libsource (lib "eagle-import") (part "resistor_348_R-EU_0207/7"))
    )
    (comp (ref "R21")
      (value "120k")
      (footprint "eagle-import:0207_7")
      (libsource (lib "eagle-import") (part "resistor_348_R-EU_0207/7"))
    )
    (comp (ref "R22")
      (value "120k")
      (footprint "eagle-import:0207_7")
      (libsource (lib "eagle-import") (part "resistor_348_R-EU_0207/7"))
    )
    (comp (ref "R23")
      (value "120k")
      (footprint "eagle-import:0207_7")
      (libsource (lib "eagle-import") (part "resistor_348_R-EU_0207/7"))
    )
    (comp (ref "R24")
      (value "120k")
      (footprint "eagle-import:0207_7")
      (libsource (lib "eagle-import") (part "resistor_348_R-EU_0207/7"))
    )
    (comp (ref "R25")
      (value "120k")
      (footprint "eagle-import:0207_7")
      (libsource (lib "eagle-import") (part "resistor_348_R-EU_0207/7"))
    )
    (comp (ref "R26")
      (value "120k")
      (footprint "eagle-import:0207_7")
      (libsource (lib "eagle-import") (part "resistor_348_R-EU_0207/7"))
    )
    (comp (ref "R27")
      (value "1M")
      (footprint "eagle-import:0207_7")
      (libsource (lib "eagle-import") (part "resistor_348_R-EU_0207/7"))
    )
    (comp (ref "R28")
      (value "1M")
      (footprint "eagle-import:0207_7")
      (libsource (lib "eagle-import") (part "resistor_348_R-EU_0207/7"))
    )
    (comp (ref "R29")
      (value "1M")
      (footprint "eagle-import:0207_7")
      (libsource (lib "eagle-import") (part "resistor_348_R-EU_0207/7"))
    )
    (comp (ref "R30")
      (value "1M")
      (footprint "eagle-import:0207_7")
      (libsource (lib "eagle-import") (part "resistor_348_R-EU_0207/7"))
    )
    (comp (ref "R31")
      (value "120k")
      (footprint "eagle-import:0207_7")
      (libsource (lib "eagle-import") (part "resistor_348_R-EU_0207/7"))
    )
    (comp (ref "R32")
      (value "120k")
      (footprint "eagle-import:0207_7")
      (libsource (lib "eagle-import") (part "resistor_348_R-EU_0207/7"))
    )
    (comp (ref "R33")
      (value "120k")
      (footprint "eagle-import:0207_7")
      (libsource (lib "eagle-import") (part "resistor_348_R-EU_0207/7"))
    )
    (comp (ref "R34")
      (value "120k")
      (footprint "eagle-import:0207_7")
      (libsource (lib "eagle-import") (part "resistor_348_R-EU_0207/7"))
    )
    (comp (ref "R35")
      (value "120k")
      (footprint "eagle-import:0207_7")
      (libsource (lib "eagle-import") (part "resistor_348_R-EU_0207/7"))
    )
    (comp (ref "R36")
      (value "120k")
      (footprint "eagle-import:0207_7")
      (libsource (lib "eagle-import") (part "resistor_348_R-EU_0207/7"))
    )
    (comp (ref "R37")
      (value "120k")
      (footprint "eagle-import:0207_7")
      (libsource (lib "eagle-import") (part "resistor_348_R-EU_0207/7"))
    )
    (comp (ref "R38")
      (value "120k")
      (footprint "eagle-import:0207_7")
      (libsource (lib "eagle-import") (part "resistor_348_R-EU_0207/7"))
    )
    (comp (ref "R39")
      (value "1M")
      (footprint "eagle-import:0207_7")
      (libsource (lib "eagle-import") (part "resistor_348_R-EU_0207/7"))
    )
    (comp (ref "R40")
      (value "1M")
      (footprint "eagle-import:0207_7")
      (libsource (lib "eagle-import") (part "resistor_348_R-EU_0207/7"))
    )
    (comp (ref "R41")
      (value "1M")
      (footprint "eagle-import:0207_7")
      (libsource (lib "eagle-import") (part "resistor_348_R-EU_0207/7"))
    )
    (comp (ref "R42")
      (value "1M")
      (footprint "eagle-import:0207_7")
      (libsource (lib "eagle-import") (part "resistor_348_R-EU_0207/7"))
    )
    (comp (ref "C40")
      (value "100n")
      (footprint "eagle-import:C050-024X044")
      (libsource (lib "eagle-import") (part "C-EU050-024X044"))
    )
    (comp (ref "C41")
      (value "100n")
      (footprint "eagle-import:C050-024X044")
      (libsource (lib "eagle-import") (part "C-EU050-024X044"))
    )
    (comp (ref "C42")
      (value "100n")
      (footprint "eagle-import:C050-024X044")
      (libsource (lib "eagle-import") (part "C-EU050-024X044"))
    )
    (comp (ref "C43")
      (value "100n")
      (footprint "eagle-import:C050-024X044")
      (libsource (lib "eagle-import") (part "C-EU050-024X044"))
    )
    (comp (ref "DIS5")
      (value "SHB10R")
      (footprint "eagle-import:SHB10R")
      (libsource (lib "eagle-import") (part "SHB10R"))
    )
    (comp (ref "DIS6")
      (value "SHB10R")
      (footprint "eagle-import:SHB10R")
      (libsource (lib "eagle-import") (part "SHB10R"))
    )
    (comp (ref "DIS7")
      (value "SHB10R")
      (footprint "eagle-import:SHB10R")
      (libsource (lib "eagle-import") (part "SHB10R"))
    )
    (comp (ref "DIS8")
      (value "SHB10R")
      (footprint "eagle-import:SHB10R")
      (libsource (lib "eagle-import") (part "SHB10R"))
    )
    (comp (ref "IC8")
      (value "LM3914N")
      (footprint "eagle-import:DIL18")
      (libsource (lib "eagle-import") (part "LM3914N"))
    )
    (comp (ref "IC9")
      (value "LM3914N")
      (footprint "eagle-import:DIL18")
      (libsource (lib "eagle-import") (part "LM3914N"))
    )
    (comp (ref "IC10")
      (value "LM3914N")
      (footprint "eagle-import:DIL18")
      (libsource (lib "eagle-import") (part "LM3914N"))
    )
    (comp (ref "IC11")
      (value "LM3914N")
      (footprint "eagle-import:DIL18")
      (libsource (lib "eagle-import") (part "LM3914N"))
    )
    (comp (ref "R51")
      (value "1k2")
      (footprint "eagle-import:0207_7")
      (libsource (lib "eagle-import") (part "resistor_348_R-EU_0207/7"))
    )
    (comp (ref "R52")
      (value "7k5")
      (footprint "eagle-import:0207_7")
      (libsource (lib "eagle-import") (part "resistor_348_R-EU_0207/7"))
    )
    (comp (ref "R53")
      (value "1k2")
      (footprint "eagle-import:0207_7")
      (libsource (lib "eagle-import") (part "resistor_348_R-EU_0207/7"))
    )
    (comp (ref "R54")
      (value "7k5")
      (footprint "eagle-import:0207_7")
      (libsource (lib "eagle-import") (part "resistor_348_R-EU_0207/7"))
    )
    (comp (ref "R55")
      (value "1k2")
      (footprint "eagle-import:0207_7")
      (libsource (lib "eagle-import") (part "resistor_348_R-EU_0207/7"))
    )
    (comp (ref "R56")
      (value "7k5")
      (footprint "eagle-import:0207_7")
      (libsource (lib "eagle-import") (part "resistor_348_R-EU_0207/7"))
    )
    (comp (ref "R57")
      (value "1k2")
      (footprint "eagle-import:0207_7")
      (libsource (lib "eagle-import") (part "resistor_348_R-EU_0207/7"))
    )
    (comp (ref "R58")
      (value "7k5")
      (footprint "eagle-import:0207_7")
      (libsource (lib "eagle-import") (part "resistor_348_R-EU_0207/7"))
    )
  )
  (nets
    (net (code "1") (name "+5V") (class "Default")
      (node (ref "C2") (pin "1") (pinfunction "1_1") (pintype "passive"))
      (node (ref "C36") (pin "1") (pinfunction "1_1") (pintype "passive"))
      (node (ref "C37") (pin "1") (pinfunction "1_1") (pintype "passive"))
      (node (ref "C38") (pin "1") (pinfunction "1_1") (pintype "passive"))
      (node (ref "C39") (pin "1") (pinfunction "1_1") (pintype "passive"))
      (node (ref "C4") (pin "1") (pinfunction "1_1") (pintype "passive"))
      (node (ref "C40") (pin "1") (pinfunction "1_1") (pintype "passive"))
      (node (ref "C41") (pin "1") (pinfunction "1_1") (pintype "passive"))
      (node (ref "C42") (pin "1") (pinfunction "1_1") (pintype "passive"))
      (node (ref "C43") (pin "1") (pinfunction "1_1") (pintype "passive"))
      (node (ref "C44") (pin "1") (pinfunction "1_1") (pintype "passive"))
      (node (ref "C45") (pin "1") (pinfunction "1_1") (pintype "passive"))
      (node (ref "C5") (pin "1") (pinfunction "1_1") (pintype "passive"))
      (node (ref "DIS1") (pin "1") (pinfunction "1_1") (pintype "bidirectional"))
      (node (ref "DIS1") (pin "10") (pinfunction "10_10") (pintype "bidirectional"))
      (node (ref "DIS1") (pin "2") (pinfunction "2_2") (pintype "bidirectional"))
      (node (ref "DIS1") (pin "3") (pinfunction "3_3") (pintype "bidirectional"))
      (node (ref "DIS1") (pin "4") (pinfunction "4_4") (pintype "bidirectional"))
      (node (ref "DIS1") (pin "5") (pinfunction "5_5") (pintype "bidirectional"))
      (node (ref "DIS1") (pin "6") (pinfunction "6_6") (pintype "bidirectional"))
      (node (ref "DIS1") (pin "7") (pinfunction "7_7") (pintype "bidirectional"))
      (node (ref "DIS1") (pin "8") (pinfunction "8_8") (pintype "bidirectional"))
      (node (ref "DIS1") (pin "9") (pinfunction "9_9") (pintype "bidirectional"))
      (node (ref "DIS10") (pin "1") (pinfunction "1_1") (pintype "bidirectional"))
      (node (ref "DIS10") (pin "10") (pinfunction "10_10") (pintype "bidirectional"))
      (node (ref "DIS10") (pin "2") (pinfunction "2_2") (pintype "bidirectional"))
      (node (ref "DIS10") (pin "3") (pinfunction "3_3") (pintype "bidirectional"))
      (node (ref "DIS10") (pin "4") (pinfunction "4_4") (pintype "bidirectional"))
      (node (ref "DIS10") (pin "5") (pinfunction "5_5") (pintype "bidirectional"))
      (node (ref "DIS10") (pin "6") (pinfunction "6_6") (pintype "bidirectional"))
      (node (ref "DIS10") (pin "7") (pinfunction "7_7") (pintype "bidirectional"))
      (node (ref "DIS10") (pin "8") (pinfunction "8_8") (pintype "bidirectional"))
      (node (ref "DIS10") (pin "9") (pinfunction "9_9") (pintype "bidirectional"))
      (node (ref "DIS2") (pin "1") (pinfunction "1_1") (pintype "bidirectional"))
      (node (ref "DIS2") (pin "10") (pinfunction "10_10") (pintype "bidirectional"))
      (node (ref "DIS2") (pin "2") (pinfunction "2_2") (pintype "bidirectional"))
      (node (ref "DIS2") (pin "3") (pinfunction "3_3") (pintype "bidirectional"))
      (node (ref "DIS2") (pin "4") (pinfunction "4_4") (pintype "bidirectional"))
      (node (ref "DIS2") (pin "5") (pinfunction "5_5") (pintype "bidirectional"))
      (node (ref "DIS2") (pin "6") (pinfunction "6_6") (pintype "bidirectional"))
      (node (ref "DIS2") (pin "7") (pinfunction "7_7") (pintype "bidirectional"))
      (node (ref "DIS2") (pin "8") (pinfunction "8_8") (pintype "bidirectional"))
      (node (ref "DIS2") (pin "9") (pinfunction "9_9") (pintype "bidirectional"))
      (node (ref "DIS3") (pin "1") (pinfunction "1_1") (pintype "bidirectional"))
      (node (ref "DIS3") (pin "10") (pinfunction "10_10") (pintype "bidirectional"))
      (node (ref "DIS3") (pin "2") (pinfunction "2_2") (pintype "bidirectional"))
      (node (ref "DIS3") (pin "3") (pinfunction "3_3") (pintype "bidirectional"))
      (node (ref "DIS3") (pin "4") (pinfunction "4_4") (pintype "bidirectional"))
      (node (ref "DIS3") (pin "5") (pinfunction "5_5") (pintype "bidirectional"))
      (node (ref "DIS3") (pin "6") (pinfunction "6_6") (pintype "bidirectional"))
      (node (ref "DIS3") (pin "7") (pinfunction "7_7") (pintype "bidirectional"))
      (node (ref "DIS3") (pin "8") (pinfunction "8_8") (pintype "bidirectional"))
      (node (ref "DIS3") (pin "9") (pinfunction "9_9") (pintype "bidirectional"))
      (node (ref "DIS4") (pin "1") (pinfunction "1_1") (pintype "bidirectional"))
      (node (ref "DIS4") (pin "10") (pinfunction "10_10") (pintype "bidirectional"))
      (node (ref "DIS4") (pin "2") (pinfunction "2_2") (pintype "bidirectional"))
      (node (ref "DIS4") (pin "3") (pinfunction "3_3") (pintype "bidirectional"))
      (node (ref "DIS4") (pin "4") (pinfunction "4_4") (pintype "bidirectional"))
      (node (ref "DIS4") (pin "5") (pinfunction "5_5") (pintype "bidirectional"))
      (node (ref "DIS4") (pin "6") (pinfunction "6_6") (pintype "bidirectional"))
      (node (ref "DIS4") (pin "7") (pinfunction "7_7") (pintype "bidirectional"))
      (node (ref "DIS4") (pin "8") (pinfunction "8_8") (pintype "bidirectional"))
      (node (ref "DIS4") (pin "9") (pinfunction "9_9") (pintype "bidirectional"))
      (node (ref "DIS5") (pin "1") (pinfunction "1_1") (pintype "bidirectional"))
      (node (ref "DIS5") (pin "10") (pinfunction "10_10") (pintype "bidirectional"))
      (node (ref "DIS5") (pin "2") (pinfunction "2_2") (pintype "bidirectional"))
      (node (ref "DIS5") (pin "3") (pinfunction "3_3") (pintype "bidirectional"))
      (node (ref "DIS5") (pin "4") (pinfunction "4_4") (pintype "bidirectional"))
      (node (ref "DIS5") (pin "5") (pinfunction "5_5") (pintype "bidirectional"))
      (node (ref "DIS5") (pin "6") (pinfunction "6_6") (pintype "bidirectional"))
      (node (ref "DIS5") (pin "7") (pinfunction "7_7") (pintype "bidirectional"))
      (node (ref "DIS5") (pin "8") (pinfunction "8_8") (pintype "bidirectional"))
      (node (ref "DIS5") (pin "9") (pinfunction "9_9") (pintype "bidirectional"))
      (node (ref "DIS6") (pin "1") (pinfunction "1_1") (pintype "bidirectional"))
      (node (ref "DIS6") (pin "10") (pinfunction "10_10") (pintype "bidirectional"))
      (node (ref "DIS6") (pin "2") (pinfunction "2_2") (pintype "bidirectional"))
      (node (ref "DIS6") (pin "3") (pinfunction "3_3") (pintype "bidirectional"))
      (node (ref "DIS6") (pin "4") (pinfunction "4_4") (pintype "bidirectional"))
      (node (ref "DIS6") (pin "5") (pinfunction "5_5") (pintype "bidirectional"))
      (node (ref "DIS6") (pin "6") (pinfunction "6_6") (pintype "bidirectional"))
      (node (ref "DIS6") (pin "7") (pinfunction "7_7") (pintype "bidirectional"))
      (node (ref "DIS6") (pin "8") (pinfunction "8_8") (pintype "bidirectional"))
      (node (ref "DIS6") (pin "9") (pinfunction "9_9") (pintype "bidirectional"))
      (node (ref "DIS7") (pin "1") (pinfunction "1_1") (pintype "bidirectional"))
      (node (ref "DIS7") (pin "10") (pinfunction "10_10") (pintype "bidirectional"))
      (node (ref "DIS7") (pin "2") (pinfunction "2_2") (pintype "bidirectional"))
      (node (ref "DIS7") (pin "3") (pinfunction "3_3") (pintype "bidirectional"))
      (node (ref "DIS7") (pin "4") (pinfunction "4_4") (pintype "bidirectional"))
      (node (ref "DIS7") (pin "5") (pinfunction "5_5") (pintype "bidirectional"))
      (node (ref "DIS7") (pin "6") (pinfunction "6_6") (pintype "bidirectional"))
      (node (ref "DIS7") (pin "7") (pinfunction "7_7") (pintype "bidirectional"))
      (node (ref "DIS7") (pin "8") (pinfunction "8_8") (pintype "bidirectional"))
      (node (ref "DIS7") (pin "9") (pinfunction "9_9") (pintype "bidirectional"))
      (node (ref "DIS8") (pin "1") (pinfunction "1_1") (pintype "bidirectional"))
      (node (ref "DIS8") (pin "10") (pinfunction "10_10") (pintype "bidirectional"))
      (node (ref "DIS8") (pin "2") (pinfunction "2_2") (pintype "bidirectional"))
      (node (ref "DIS8") (pin "3") (pinfunction "3_3") (pintype "bidirectional"))
      (node (ref "DIS8") (pin "4") (pinfunction "4_4") (pintype "bidirectional"))
      (node (ref "DIS8") (pin "5") (pinfunction "5_5") (pintype "bidirectional"))
      (node (ref "DIS8") (pin "6") (pinfunction "6_6") (pintype "bidirectional"))
      (node (ref "DIS8") (pin "7") (pinfunction "7_7") (pintype "bidirectional"))
      (node (ref "DIS8") (pin "8") (pinfunction "8_8") (pintype "bidirectional"))
      (node (ref "DIS8") (pin "9") (pinfunction "9_9") (pintype "bidirectional"))
      (node (ref "DIS9") (pin "1") (pinfunction "1_1") (pintype "bidirectional"))
      (node (ref "DIS9") (pin "10") (pinfunction "10_10") (pintype "bidirectional"))
      (node (ref "DIS9") (pin "2") (pinfunction "2_2") (pintype "bidirectional"))
      (node (ref "DIS9") (pin "3") (pinfunction "3_3") (pintype "bidirectional"))
      (node (ref "DIS9") (pin "4") (pinfunction "4_4") (pintype "bidirectional"))
      (node (ref "DIS9") (pin "5") (pinfunction "5_5") (pintype "bidirectional"))
      (node (ref "DIS9") (pin "6") (pinfunction "6_6") (pintype "bidirectional"))
      (node (ref "DIS9") (pin "7") (pinfunction "7_7") (pintype "bidirectional"))
      (node (ref "DIS9") (pin "8") (pinfunction "8_8") (pintype "bidirectional"))
      (node (ref "DIS9") (pin "9") (pinfunction "9_9") (pintype "bidirectional"))
      (node (ref "IC1") (pin "4") (pinfunction "V+_4") (pintype "power_in"))
      (node (ref "IC10") (pin "3") (pinfunction "V+_3") (pintype "power_in"))
      (node (ref "IC10") (pin "9") (pinfunction "MDE_9") (pintype "input"))
      (node (ref "IC11") (pin "3") (pinfunction "V+_3") (pintype "power_in"))
      (node (ref "IC11") (pin "9") (pinfunction "MDE_9") (pintype "input"))
      (node (ref "IC12") (pin "3") (pinfunction "V+_3") (pintype "power_in"))
      (node (ref "IC12") (pin "9") (pinfunction "MDE_9") (pintype "input"))
      (node (ref "IC13") (pin "3") (pinfunction "V+_3") (pintype "power_in"))
      (node (ref "IC13") (pin "9") (pinfunction "MDE_9") (pintype "input"))
      (node (ref "IC2") (pin "4") (pinfunction "V+_4") (pintype "power_in"))
      (node (ref "IC3") (pin "4") (pinfunction "V+_4") (pintype "power_in"))
      (node (ref "IC4") (pin "3") (pinfunction "V+_3") (pintype "power_in"))
      (node (ref "IC4") (pin "9") (pinfunction "MDE_9") (pintype "input"))
      (node (ref "IC5") (pin "3") (pinfunction "V+_3") (pintype "power_in"))
      (node (ref "IC5") (pin "9") (pinfunction "MDE_9") (pintype "input"))
      (node (ref "IC6") (pin "3") (pinfunction "V+_3") (pintype "power_in"))
      (node (ref "IC6") (pin "9") (pinfunction "MDE_9") (pintype "input"))
      (node (ref "IC7") (pin "3") (pinfunction "V+_3") (pintype "power_in"))
      (node (ref "IC7") (pin "9") (pinfunction "MDE_9") (pintype "input"))
      (node (ref "IC8") (pin "3") (pinfunction "V+_3") (pintype "power_in"))
      (node (ref "IC8") (pin "9") (pinfunction "MDE_9") (pintype "input"))
      (node (ref "IC9") (pin "3") (pinfunction "V+_3") (pintype "power_in"))
      (node (ref "IC9") (pin "9") (pinfunction "MDE_9") (pintype "input"))
      (node (ref "J2") (pin "1") (pinfunction "1_1") (pintype "passive"))
      (node (ref "R1") (pin "E") (pinfunction "E_E") (pintype "passive"))
      (node (ref "R16") (pin "2") (pinfunction "2_2") (pintype "passive"))
      (node (ref "R4") (pin "2") (pinfunction "2_2") (pintype "passive"))
      (node (ref "TP3") (pin "TP") (pinfunction "TP_TP") (pintype "input"))
    )
    (net (code "2") (name "GND") (class "Default")
      (node (ref "C10") (pin "-") (pinfunction "-_-") (pintype "passive"))
      (node (ref "C11") (pin "-") (pinfunction "-_-") (pintype "passive"))
      (node (ref "C2") (pin "2") (pinfunction "2_2") (pintype "passive"))
      (node (ref "C20") (pin "-") (pinfunction "-_-") (pintype "passive"))
      (node (ref "C21") (pin "-") (pinfunction "-_-") (pintype "passive"))
      (node (ref "C22") (pin "-") (pinfunction "-_-") (pintype "passive"))
      (node (ref "C23") (pin "-") (pinfunction "-_-") (pintype "passive"))
      (node (ref "C32") (pin "-") (pinfunction "-_-") (pintype "passive"))
      (node (ref "C33") (pin "-") (pinfunction "-_-") (pintype "passive"))
      (node (ref "C34") (pin "-") (pinfunction "-_-") (pintype "passive"))
      (node (ref "C35") (pin "-") (pinfunction "-_-") (pintype "passive"))
      (node (ref "C36") (pin "2") (pinfunction "2_2") (pintype "passive"))
      (node (ref "C37") (pin "2") (pinfunction "2_2") (pintype "passive"))
      (node (ref "C38") (pin "2") (pinfunction "2_2") (pintype "passive"))
      (node (ref "C39") (pin "2") (pinfunction "2_2") (pintype "passive"))
      (node (ref "C4") (pin "2") (pinfunction "2_2") (pintype "passive"))
      (node (ref "C40") (pin "2") (pinfunction "2_2") (pintype "passive"))
      (node (ref "C41") (pin "2") (pinfunction "2_2") (pintype "passive"))
      (node (ref "C42") (pin "2") (pinfunction "2_2") (pintype "passive"))
      (node (ref "C43") (pin "2") (pinfunction "2_2") (pintype "passive"))
      (node (ref "C44") (pin "2") (pinfunction "2_2") (pintype "passive"))
      (node (ref "C45") (pin "2") (pinfunction "2_2") (pintype "passive"))
      (node (ref "C5") (pin "2") (pinfunction "2_2") (pintype "passive"))
      (node (ref "D7") (pin "C") (pinfunction "C_C") (pintype "passive"))
      (node (ref "IC1") (pin "11") (pinfunction "V-_11") (pintype "power_in"))
      (node (ref "IC10") (pin "2") (pinfunction "V-_2") (pintype "power_in"))
      (node (ref "IC10") (pin "4") (pinfunction "RLO_4") (pintype "input"))
      (node (ref "IC11") (pin "2") (pinfunction "V-_2") (pintype "power_in"))
      (node (ref "IC11") (pin "4") (pinfunction "RLO_4") (pintype "input"))
      (node (ref "IC12") (pin "2") (pinfunction "V-_2") (pintype "power_in"))
      (node (ref "IC12") (pin "4") (pinfunction "RLO_4") (pintype "input"))
      (node (ref "IC13") (pin "2") (pinfunction "V-_2") (pintype "power_in"))
      (node (ref "IC13") (pin "4") (pinfunction "RLO_4") (pintype "input"))
      (node (ref "IC2") (pin "11") (pinfunction "V-_11") (pintype "power_in"))
      (node (ref "IC3") (pin "11") (pinfunction "V-_11") (pintype "power_in"))
      (node (ref "IC4") (pin "2") (pinfunction "V-_2") (pintype "power_in"))
      (node (ref "IC4") (pin "4") (pinfunction "RLO_4") (pintype "input"))
      (node (ref "IC5") (pin "2") (pinfunction "V-_2") (pintype "power_in"))
      (node (ref "IC5") (pin "4") (pinfunction "RLO_4") (pintype "input"))
      (node (ref "IC6") (pin "2") (pinfunction "V-_2") (pintype "power_in"))
      (node (ref "IC6") (pin "4") (pinfunction "RLO_4") (pintype "input"))
      (node (ref "IC7") (pin "2") (pinfunction "V-_2") (pintype "power_in"))
      (node (ref "IC7") (pin "4") (pinfunction "RLO_4") (pintype "input"))
      (node (ref "IC8") (pin "2") (pinfunction "V-_2") (pintype "power_in"))
      (node (ref "IC8") (pin "4") (pinfunction "RLO_4") (pintype "input"))
      (node (ref "IC9") (pin "2") (pinfunction "V-_2") (pintype "power_in"))
      (node (ref "IC9") (pin "4") (pinfunction "RLO_4") (pintype "input"))
      (node (ref "J1") (pin "1") (pinfunction "GND_1") (pintype "power_in"))
      (node (ref "J2") (pin "3") (pinfunction "3_3") (pintype "passive"))
      (node (ref "M1") (pin "1") (pinfunction "1_1") (pintype "passive"))
      (node (ref "R14") (pin "1") (pinfunction "1_1") (pintype "passive"))
      (node (ref "R15") (pin "1") (pinfunction "1_1") (pintype "passive"))
      (node (ref "R23") (pin "1") (pinfunction "1_1") (pintype "passive"))
      (node (ref "R24") (pin "1") (pinfunction "1_1") (pintype "passive"))
      (node (ref "R25") (pin "1") (pinfunction "1_1") (pintype "passive"))
      (node (ref "R26") (pin "1") (pinfunction "1_1") (pintype "passive"))
      (node (ref "R35") (pin "1") (pinfunction "1_1") (pintype "passive"))
      (node (ref "R36") (pin "1") (pinfunction "1_1") (pintype "passive"))
      (node (ref "R37") (pin "1") (pinfunction "1_1") (pintype "passive"))
      (node (ref "R38") (pin "1") (pinfunction "1_1") (pintype "passive"))
      (node (ref "R44") (pin "1") (pinfunction "1_1") (pintype "passive"))
      (node (ref "R46") (pin "1") (pinfunction "1_1") (pintype "passive"))
      (node (ref "R48") (pin "1") (pinfunction "1_1") (pintype "passive"))
      (node (ref "R5") (pin "1") (pinfunction "1_1") (pintype "passive"))
      (node (ref "R50") (pin "1") (pinfunction "1_1") (pintype "passive"))
      (node (ref "R52") (pin "1") (pinfunction "1_1") (pintype "passive"))
      (node (ref "R54") (pin "1") (pinfunction "1_1") (pintype "passive"))
      (node (ref "R56") (pin "1") (pinfunction "1_1") (pintype "passive"))
      (node (ref "R58") (pin "1") (pinfunction "1_1") (pintype "passive"))
      (node (ref "R6") (pin "1") (pinfunction "1_1") (pintype "passive"))
      (node (ref "R60") (pin "1") (pinfunction "1_1") (pintype "passive"))
      (node (ref "R62") (pin "1") (pinfunction "1_1") (pintype "passive"))
      (node (ref "R7") (pin "1") (pinfunction "1_1") (pintype "passive"))
      (node (ref "TP2") (pin "TP") (pinfunction "TP_TP") (pintype "input"))
    )
    (net (code "3") (name "Net-(C1-Pad+)") (class "Default")
      (node (ref "C1") (pin "+") (pinfunction "+_+") (pintype "passive"))
      (node (ref "M1") (pin "2") (pinfunction "2_2") (pintype "passive"))
      (node (ref "R1") (pin "S") (pinfunction "S_S") (pintype "passive"))
    )
    (net (code "4") (name "Net-(C3-Pad+)") (class "Default")
      (node (ref "C3") (pin "+") (pinfunction "+_+") (pintype "passive"))
      (node (ref "S1") (pin "2") (pinfunction "2_2") (pintype "passive"))
    )
    (net (code "5") (name "Net-(C6-Pad1)") (class "Default")
      (node (ref "C6") (pin "1") (pinfunction "1_1") (pintype "passive"))
      (node (ref "C8") (pin "1") (pinfunction "1_1") (pintype "passive"))
      (node (ref "R12") (pin "2") (pinfunction "2_2") (pintype "passive"))
      (node (ref "R14") (pin "2") (pinfunction "2_2") (pintype "passive"))
    )
    (net (code "6") (name "Net-(C7-Pad1)") (class "Default")
      (node (ref "C7") (pin "1") (pinfunction "1_1") (pintype "passive"))
      (node (ref "C9") (pin "1") (pinfunction "1_1") (pintype "passive"))
      (node (ref "R13") (pin "2") (pinfunction "2_2") (pintype "passive"))
      (node (ref "R15") (pin "2") (pinfunction "2_2") (pintype "passive"))
    )
    (net (code "7") (name "Net-(C12-Pad1)") (class "Default")
      (node (ref "C12") (pin "1") (pinfunction "1_1") (pintype "passive"))
      (node (ref "C16") (pin "1") (pinfunction "1_1") (pintype "passive"))
      (node (ref "R19") (pin "2") (pinfunction "2_2") (pintype "passive"))
      (node (ref "R23") (pin "2") (pinfunction "2_2") (pintype "passive"))
    )
    (net (code "8") (name "Net-(C13-Pad1)") (class "Default")
      (node (ref "C13") (pin "1") (pinfunction "1_1") (pintype "passive"))
      (node (ref "C17") (pin "1") (pinfunction "1_1") (pintype "passive"))
      (node (ref "R20") (pin "2") (pinfunction "2_2") (pintype "passive"))
      (node (ref "R24") (pin "2") (pinfunction "2_2") (pintype "passive"))
    )
    (net (code "9") (name "Net-(C14-Pad1)") (class "Default")
      (node (ref "C14") (pin "1") (pinfunction "1_1") (pintype "passive"))
      (node (ref "C18") (pin "1") (pinfunction "1_1") (pintype "passive"))
      (node (ref "R21") (pin "2") (pinfunction "2_2") (pintype "passive"))
      (node (ref "R25") (pin "2") (pinfunction "2_2") (pintype "passive"))
    )
    (net (code "10") (name "Net-(C15-Pad1)") (class "Default")
      (node (ref "C15") (pin "1") (pinfunction "1_1") (pintype "passive"))
      (node (ref "C19") (pin "1") (pinfunction "1_1") (pintype "passive"))
      (node (ref "R22") (pin "2") (pinfunction "2_2") (pintype "passive"))
      (node (ref "R26") (pin "2") (pinfunction "2_2") (pintype "passive"))
    )
    (net (code "11") (name "Net-(C24-Pad1)") (class "Default")
      (node (ref "C24") (pin "1") (pinfunction "1_1") (pintype "passive"))
      (node (ref "C28") (pin "1") (pinfunction "1_1") (pintype "passive"))
      (node (ref "R31") (pin "2") (pinfunction "2_2") (pintype "passive"))
      (node (ref "R35") (pin "2") (pinfunction "2_2") (pintype "passive"))
    )
    (net (code "12") (name "Net-(C25-Pad1)") (class "Default")
      (node (ref "C25") (pin "1") (pinfunction "1_1") (pintype "passive"))
      (node (ref "C29") (pin "1") (pinfunction "1_1") (pintype "passive"))
      (node (ref "R32") (pin "2") (pinfunction "2_2") (pintype "passive"))
      (node (ref "R36") (pin "2") (pinfunction "2_2") (pintype "passive"))
    )
    (net (code "13") (name "Net-(C26-Pad1)") (class "Default")
      (node (ref "C26") (pin "1") (pinfunction "1_1") (pintype "passive"))
      (node (ref "C30") (pin "1") (pinfunction "1_1") (pintype "passive"))
      (node (ref "R33") (pin "2") (pinfunction "2_2") (pintype "passive"))
      (node (ref "R37") (pin "2") (pinfunction "2_2") (pintype "passive"))
    )
    (net (code "14") (name "Net-(C27-Pad1)") (class "Default")
      (node (ref "C27") (pin "1") (pinfunction "1_1") (pintype "passive"))
      (node (ref "C31") (pin "1") (pinfunction "1_1") (pintype "passive"))
      (node (ref "R34") (pin "2") (pinfunction "2_2") (pintype "passive"))
      (node (ref "R38") (pin "2") (pinfunction "2_2") (pintype "passive"))
    )
    (net (code "15") (name "Net-(IC1A-+IN)") (class "Default")
      (node (ref "C1") (pin "-") (pinfunction "-_-") (pintype "passive"))
      (node (ref "IC1") (pin "3") (pinfunction "+IN_3") (pintype "input"))
      (node (ref "R4") (pin "1") (pinfunction "1_1") (pintype "passive"))
      (node (ref "R5") (pin "2") (pinfunction "2_2") (pintype "passive"))
    )
    (net (code "16") (name "Net-(IC1A--IN)") (class "Default")
      (node (ref "IC1") (pin "2") (pinfunction "-IN_2") (pintype "input"))
      (node (ref "R6") (pin "2") (pinfunction "2_2") (pintype "passive"))
      (node (ref "R8") (pin "1") (pinfunction "1_1") (pintype "passive"))
    )
    (net (code "17") (name "Net-(IC1A-OUT)") (class "Default")
      (node (ref "IC1") (pin "1") (pinfunction "OUT_1") (pintype "output"))
      (node (ref "R10") (pin "E") (pinfunction "E_E") (pintype "passive"))
      (node (ref "S1") (pin "1") (pinfunction "1_1") (pintype "passive"))
    )
    (net (code "18") (name "Net-(IC1B-+IN)") (class "Default")
      (node (ref "IC1") (pin "5") (pinfunction "+IN_5") (pintype "input"))
      (node (ref "R2") (pin "2") (pinfunction "2_2") (pintype "passive"))
      (node (ref "R3") (pin "2") (pinfunction "2_2") (pintype "passive"))
    )
    (net (code "19") (name "Net-(IC1B--IN)") (class "Default")
      (node (ref "IC1") (pin "6") (pinfunction "-IN_6") (pintype "input"))
      (node (ref "R7") (pin "2") (pinfunction "2_2") (pintype "passive"))
      (node (ref "R9") (pin "1") (pinfunction "1_1") (pintype "passive"))
    )
    (net (code "20") (name "Net-(IC1B-OUT)") (class "Default")
      (node (ref "IC1") (pin "7") (pinfunction "OUT_7") (pintype "output"))
      (node (ref "R11") (pin "E") (pinfunction "E_E") (pintype "passive"))
      (node (ref "S1") (pin "3") (pinfunction "3_3") (pintype "passive"))
    )
    (net (code "21") (name "Net-(IC1C--IN)") (class "Default")
      (node (ref "C6") (pin "2") (pinfunction "2_2") (pintype "passive"))
      (node (ref "IC1") (pin "9") (pinfunction "-IN_9") (pintype "input"))
      (node (ref "R17") (pin "1") (pinfunction "1_1") (pintype "passive"))
    )
    (net (code "22") (name "Net-(IC1C-OUT)") (class "Default")
      (node (ref "C8") (pin "2") (pinfunction "2_2") (pintype "passive"))
      (node (ref "D1") (pin "A") (pinfunction "A_A") (pintype "passive"))
      (node (ref "IC1") (pin "8") (pinfunction "OUT_8") (pintype "output"))
      (node (ref "R17") (pin "2") (pinfunction "2_2") (pintype "passive"))
    )
    (net (code "23") (name "Net-(IC1D--IN)") (class "Default")
      (node (ref "C7") (pin "2") (pinfunction "2_2") (pintype "passive"))
      (node (ref "IC1") (pin "13") (pinfunction "-IN_13") (pintype "input"))
      (node (ref "R18") (pin "1") (pinfunction "1_1") (pintype "passive"))
    )
    (net (code "24") (name "Net-(IC1D-OUT)") (class "Default")
      (node (ref "C9") (pin "2") (pinfunction "2_2") (pintype "passive"))
      (node (ref "D2") (pin "A") (pinfunction "A_A") (pintype "passive"))
      (node (ref "IC1") (pin "14") (pinfunction "OUT_14") (pintype "output"))
      (node (ref "R18") (pin "2") (pinfunction "2_2") (pintype "passive"))
    )
    (net (code "25") (name "Net-(IC2A--IN)") (class "Default")
      (node (ref "C12") (pin "2") (pinfunction "2_2") (pintype "passive"))
      (node (ref "IC2") (pin "2") (pinfunction "-IN_2") (pintype "input"))
      (node (ref "R27") (pin "1") (pinfunction "1_1") (pintype "passive"))
    )
    (net (code "26") (name "Net-(IC2A-OUT)") (class "Default")
      (node (ref "C16") (pin "2") (pinfunction "2_2") (pintype "passive"))
      (node (ref "D3") (pin "A") (pinfunction "A_A") (pintype "passive"))
      (node (ref "IC2") (pin "1") (pinfunction "OUT_1") (pintype "output"))
      (node (ref "R27") (pin "2") (pinfunction "2_2") (pintype "passive"))
    )
    (net (code "27") (name "Net-(IC2B--IN)") (class "Default")
      (node (ref "C13") (pin "2") (pinfunction "2_2") (pintype "passive"))
      (node (ref "IC2") (pin "6") (pinfunction "-IN_6") (pintype "input"))
      (node (ref "R28") (pin "1") (pinfunction "1_1") (pintype "passive"))
    )
    (net (code "28") (name "Net-(IC2B-OUT)") (class "Default")
      (node (ref "C17") (pin "2") (pinfunction "2_2") (pintype "passive"))
      (node (ref "D4") (pin "A") (pinfunction "A_A") (pintype "passive"))
      (node (ref "IC2") (pin "7") (pinfunction "OUT_7") (pintype "output"))
      (node (ref "R28") (pin "2") (pinfunction "2_2") (pintype "passive"))
    )
    (net (code "29") (name "Net-(IC2C--IN)") (class "Default")
      (node (ref "C14") (pin "2") (pinfunction "2_2") (pintype "passive"))
      (node (ref "IC2") (pin "9") (pinfunction "-IN_9") (pintype "input"))
      (node (ref "R29") (pin "1") (pinfunction "1_1") (pintype "passive"))
    )
    (net (code "30") (name "Net-(IC2C-OUT)") (class "Default")
      (node (ref "C18") (pin "2") (pinfunction "2_2") (pintype "passive"))
      (node (ref "D5") (pin "A") (pinfunction "A_A") (pintype "passive"))
      (node (ref "IC2") (pin "8") (pinfunction "OUT_8") (pintype "output"))
      (node (ref "R29") (pin "2") (pinfunction "2_2") (pintype "passive"))
    )
    (net (code "31") (name "Net-(IC2D--IN)") (class "Default")
      (node (ref "C15") (pin "2") (pinfunction "2_2") (pintype "passive"))
      (node (ref "IC2") (pin "13") (pinfunction "-IN_13") (pintype "input"))
      (node (ref "R30") (pin "1") (pinfunction "1_1") (pintype "passive"))
    )
    (net (code "32") (name "Net-(IC2D-OUT)") (class "Default")
      (node (ref "C19") (pin "2") (pinfunction "2_2") (pintype "passive"))
      (node (ref "D6") (pin "A") (pinfunction "A_A") (pintype "passive"))
      (node (ref "IC2") (pin "14") (pinfunction "OUT_14") (pintype "output"))
      (node (ref "R30") (pin "2") (pinfunction "2_2") (pintype "passive"))
    )
    (net (code "33") (name "Net-(IC3A--IN)") (class "Default")
      (node (ref "C24") (pin "2") (pinfunction "2_2") (pintype "passive"))
      (node (ref "IC3") (pin "2") (pinfunction "-IN_2") (pintype "input"))
      (node (ref "R39") (pin "1") (pinfunction "1_1") (pintype "passive"))
    )
    (net (code "34") (name "Net-(IC3A-OUT)") (class "Default")
      (node (ref "C28") (pin "2") (pinfunction "2_2") (pintype "passive"))
      (node (ref "D8") (pin "A") (pinfunction "A_A") (pintype "passive"))
      (node (ref "IC3") (pin "1") (pinfunction "OUT_1") (pintype "output"))
      (node (ref "R39") (pin "2") (pinfunction "2_2") (pintype "passive"))
    )
    (net (code "35") (name "Net-(IC3B--IN)") (class "Default")
      (node (ref "C25") (pin "2") (pinfunction "2_2") (pintype "passive"))
      (node (ref "IC3") (pin "6") (pinfunction "-IN_6") (pintype "input"))
      (node (ref "R40") (pin "1") (pinfunction "1_1") (pintype "passive"))
    )
    (net (code "36") (name "Net-(IC3B-OUT)") (class "Default")
      (node (ref "C29") (pin "2") (pinfunction "2_2") (pintype "passive"))
      (node (ref "D9") (pin "A") (pinfunction "A_A") (pintype "passive"))
      (node (ref "IC3") (pin "7") (pinfunction "OUT_7") (pintype "output"))
      (node (ref "R40") (pin "2") (pinfunction "2_2") (pintype "passive"))
    )
    (net (code "37") (name "Net-(IC3C--IN)") (class "Default")
      (node (ref "C26") (pin "2") (pinfunction "2_2") (pintype "passive"))
      (node (ref "IC3") (pin "9") (pinfunction "-IN_9") (pintype "input"))
      (node (ref "R41") (pin "1") (pinfunction "1_1") (pintype "passive"))
    )
    (net (code "38") (name "Net-(IC3C-OUT)") (class "Default")
      (node (ref "C30") (pin "2") (pinfunction "2_2") (pintype "passive"))
      (node (ref "D10") (pin "A") (pinfunction "A_A") (pintype "passive"))
      (node (ref "IC3") (pin "8") (pinfunction "OUT_8") (pintype "output"))
      (node (ref "R41") (pin "2") (pinfunction "2_2") (pintype "passive"))
    )
    (net (code "39") (name "Net-(IC3D--IN)") (class "Default")
      (node (ref "C27") (pin "2") (pinfunction "2_2") (pintype "passive"))
      (node (ref "IC3") (pin "13") (pinfunction "-IN_13") (pintype "input"))
      (node (ref "R42") (pin "1") (pinfunction "1_1") (pintype "passive"))
    )
    (net (code "40") (name "Net-(IC3D-OUT)") (class "Default")
      (node (ref "C31") (pin "2") (pinfunction "2_2") (pintype "passive"))
      (node (ref "D11") (pin "A") (pinfunction "A_A") (pintype "passive"))
      (node (ref "IC3") (pin "14") (pinfunction "OUT_14") (pintype "output"))
      (node (ref "R42") (pin "2") (pinfunction "2_2") (pintype "passive"))
    )
    (net (code "41") (name "Net-(IC4-ADJ)") (class "Default")
      (node (ref "IC4") (pin "8") (pinfunction "ADJ_8") (pintype "input"))
      (node (ref "R43") (pin "1") (pinfunction "1_1") (pintype "passive"))
      (node (ref "R44") (pin "2") (pinfunction "2_2") (pintype "passive"))
    )
    (net (code "42") (name "Net-(IC4-L1)") (class "Default")
      (node (ref "DIS1") (pin "11") (pinfunction "11_11") (pintype "bidirectional"))
      (node (ref "IC4") (pin "1") (pinfunction "L1_1") (pintype "output"))
    )
    (net (code "43") (name "Net-(IC4-L2)") (class "Default")
      (node (ref "DIS1") (pin "12") (pinfunction "12_12") (pintype "bidirectional"))
      (node (ref "IC4") (pin "18") (pinfunction "L2_18") (pintype "output"))
    )
    (net (code "44") (name "Net-(IC4-L3)") (class "Default")
      (node (ref "DIS1") (pin "13") (pinfunction "13_13") (pintype "bidirectional"))
      (node (ref "IC4") (pin "17") (pinfunction "L3_17") (pintype "output"))
    )
    (net (code "45") (name "Net-(IC4-L4)") (class "Default")
      (node (ref "DIS1") (pin "14") (pinfunction "14_14") (pintype "bidirectional"))
      (node (ref "IC4") (pin "16") (pinfunction "L4_16") (pintype "output"))
    )
    (net (code "46") (name "Net-(IC4-L5)") (class "Default")
      (node (ref "DIS1") (pin "15") (pinfunction "15_15") (pintype "bidirectional"))
      (node (ref "IC4") (pin "15") (pinfunction "L5_15") (pintype "output"))
    )
    (net (code "47") (name "Net-(IC4-L6)") (class "Default")
      (node (ref "DIS1") (pin "16") (pinfunction "16_16") (pintype "bidirectional"))
      (node (ref "IC4") (pin "14") (pinfunction "L6_14") (pintype "output"))
    )
    (net (code "48") (name "Net-(IC4-L7)") (class "Default")
      (node (ref "DIS1") (pin "17") (pinfunction "17_17") (pintype "bidirectional"))
      (node (ref "IC4") (pin "13") (pinfunction "L7_13") (pintype "output"))
    )
    (net (code "49") (name "Net-(IC4-L8)") (class "Default")
      (node (ref "DIS1") (pin "18") (pinfunction "18_18") (pintype "bidirectional"))
      (node (ref "IC4") (pin "12") (pinfunction "L8_12") (pintype "output"))
    )
    (net (code "50") (name "Net-(IC4-L9)") (class "Default")
      (node (ref "DIS1") (pin "19") (pinfunction "19_19") (pintype "bidirectional"))
      (node (ref "IC4") (pin "11") (pinfunction "L9_11") (pintype "output"))
    )
    (net (code "51") (name "Net-(IC4-L10)") (class "Default")
      (node (ref "DIS1") (pin "20") (pinfunction "20_20") (pintype "bidirectional"))
      (node (ref "IC4") (pin "10") (pinfunction "L10_10") (pintype "output"))
    )
    (net (code "52") (name "Net-(IC4-RHI)") (class "Default")
      (node (ref "IC4") (pin "6") (pinfunction "RHI_6") (pintype "input"))
      (node (ref "IC4") (pin "7") (pinfunction "VR_7") (pintype "output"))
      (node (ref "R43") (pin "2") (pinfunction "2_2") (pintype "passive"))
    )
    (net (code "53") (name "Net-(IC5-ADJ)") (class "Default")
      (node (ref "IC5") (pin "8") (pinfunction "ADJ_8") (pintype "input"))
      (node (ref "R45") (pin "1") (pinfunction "1_1") (pintype "passive"))
      (node (ref "R46") (pin "2") (pinfunction "2_2") (pintype "passive"))
    )
    (net (code "54") (name "Net-(IC5-L1)") (class "Default")
      (node (ref "DIS2") (pin "11") (pinfunction "11_11") (pintype "bidirectional"))
      (node (ref "IC5") (pin "1") (pinfunction "L1_1") (pintype "output"))
    )
    (net (code "55") (name "Net-(IC5-L2)") (class "Default")
      (node (ref "DIS2") (pin "12") (pinfunction "12_12") (pintype "bidirectional"))
      (node (ref "IC5") (pin "18") (pinfunction "L2_18") (pintype "output"))
    )
    (net (code "56") (name "Net-(IC5-L3)") (class "Default")
      (node (ref "DIS2") (pin "13") (pinfunction "13_13") (pintype "bidirectional"))
      (node (ref "IC5") (pin "17") (pinfunction "L3_17") (pintype "output"))
    )
    (net (code "57") (name "Net-(IC5-L4)") (class "Default")
      (node (ref "DIS2") (pin "14") (pinfunction "14_14") (pintype "bidirectional"))
      (node (ref "IC5") (pin "16") (pinfunction "L4_16") (pintype "output"))
    )
    (net (code "58") (name "Net-(IC5-L5)") (class "Default")
      (node (ref "DIS2") (pin "15") (pinfunction "15_15") (pintype "bidirectional"))
      (node (ref "IC5") (pin "15") (pinfunction "L5_15") (pintype "output"))
    )
    (net (code "59") (name "Net-(IC5-L6)") (class "Default")
      (node (ref "DIS2") (pin "16") (pinfunction "16_16") (pintype "bidirectional"))
      (node (ref "IC5") (pin "14") (pinfunction "L6_14") (pintype "output"))
    )
    (net (code "60") (name "Net-(IC5-L7)") (class "Default")
      (node (ref "DIS2") (pin "17") (pinfunction "17_17") (pintype "bidirectional"))
      (node (ref "IC5") (pin "13") (pinfunction "L7_13") (pintype "output"))
    )
    (net (code "61") (name "Net-(IC5-L8)") (class "Default")
      (node (ref "DIS2") (pin "18") (pinfunction "18_18") (pintype "bidirectional"))
      (node (ref "IC5") (pin "12") (pinfunction "L8_12") (pintype "output"))
    )
    (net (code "62") (name "Net-(IC5-L9)") (class "Default")
      (node (ref "DIS2") (pin "19") (pinfunction "19_19") (pintype "bidirectional"))
      (node (ref "IC5") (pin "11") (pinfunction "L9_11") (pintype "output"))
    )
    (net (code "63") (name "Net-(IC5-L10)") (class "Default")
      (node (ref "DIS2") (pin "20") (pinfunction "20_20") (pintype "bidirectional"))
      (node (ref "IC5") (pin "10") (pinfunction "L10_10") (pintype "output"))
    )
    (net (code "64") (name "Net-(IC5-RHI)") (class "Default")
      (node (ref "IC5") (pin "6") (pinfunction "RHI_6") (pintype "input"))
      (node (ref "IC5") (pin "7") (pinfunction "VR_7") (pintype "output"))
      (node (ref "R45") (pin "2") (pinfunction "2_2") (pintype "passive"))
    )
    (net (code "65") (name "Net-(IC6-ADJ)") (class "Default")
      (node (ref "IC6") (pin "8") (pinfunction "ADJ_8") (pintype "input"))
      (node (ref "R47") (pin "1") (pinfunction "1_1") (pintype "passive"))
      (node (ref "R48") (pin "2") (pinfunction "2_2") (pintype "passive"))
    )
    (net (code "66") (name "Net-(IC6-L1)") (class "Default")
      (node (ref "DIS3") (pin "11") (pinfunction "11_11") (pintype "bidirectional"))
      (node (ref "IC6") (pin "1") (pinfunction "L1_1") (pintype "output"))
    )
    (net (code "67") (name "Net-(IC6-L2)") (class "Default")
      (node (ref "DIS3") (pin "12") (pinfunction "12_12") (pintype "bidirectional"))
      (node (ref "IC6") (pin "18") (pinfunction "L2_18") (pintype "output"))
    )
    (net (code "68") (name "Net-(IC6-L3)") (class "Default")
      (node (ref "DIS3") (pin "13") (pinfunction "13_13") (pintype "bidirectional"))
      (node (ref "IC6") (pin "17") (pinfunction "L3_17") (pintype "output"))
    )
    (net (code "69") (name "Net-(IC6-L4)") (class "Default")
      (node (ref "DIS3") (pin "14") (pinfunction "14_14") (pintype "bidirectional"))
      (node (ref "IC6") (pin "16") (pinfunction "L4_16") (pintype "output"))
    )
    (net (code "70") (name "Net-(IC6-L5)") (class "Default")
      (node (ref "DIS3") (pin "15") (pinfunction "15_15") (pintype "bidirectional"))
      (node (ref "IC6") (pin "15") (pinfunction "L5_15") (pintype "output"))
    )
    (net (code "71") (name "Net-(IC6-L6)") (class "Default")
      (node (ref "DIS3") (pin "16") (pinfunction "16_16") (pintype "bidirectional"))
      (node (ref "IC6") (pin "14") (pinfunction "L6_14") (pintype "output"))
    )
    (net (code "72") (name "Net-(IC6-L7)") (class "Default")
      (node (ref "DIS3") (pin "17") (pinfunction "17_17") (pintype "bidirectional"))
      (node (ref "IC6") (pin "13") (pinfunction "L7_13") (pintype "output"))
    )
    (net (code "73") (name "Net-(IC6-L8)") (class "Default")
      (node (ref "DIS3") (pin "18") (pinfunction "18_18") (pintype "bidirectional"))
      (node (ref "IC6") (pin "12") (pinfunction "L8_12") (pintype "output"))
    )
    (net (code "74") (name "Net-(IC6-L9)") (class "Default")
      (node (ref "DIS3") (pin "19") (pinfunction "19_19") (pintype "bidirectional"))
      (node (ref "IC6") (pin "11") (pinfunction "L9_11") (pintype "output"))
    )
    (net (code "75") (name "Net-(IC6-L10)") (class "Default")
      (node (ref "DIS3") (pin "20") (pinfunction "20_20") (pintype "bidirectional"))
      (node (ref "IC6") (pin "10") (pinfunction "L10_10") (pintype "output"))
    )
    (net (code "76") (name "Net-(IC6-RHI)") (class "Default")
      (node (ref "IC6") (pin "6") (pinfunction "RHI_6") (pintype "input"))
      (node (ref "IC6") (pin "7") (pinfunction "VR_7") (pintype "output"))
      (node (ref "R47") (pin "2") (pinfunction "2_2") (pintype "passive"))
    )
    (net (code "77") (name "Net-(IC7-ADJ)") (class "Default")
      (node (ref "IC7") (pin "8") (pinfunction "ADJ_8") (pintype "input"))
      (node (ref "R49") (pin "1") (pinfunction "1_1") (pintype "passive"))
      (node (ref "R50") (pin "2") (pinfunction "2_2") (pintype "passive"))
    )
    (net (code "78") (name "Net-(IC7-L1)") (class "Default")
      (node (ref "DIS4") (pin "11") (pinfunction "11_11") (pintype "bidirectional"))
      (node (ref "IC7") (pin "1") (pinfunction "L1_1") (pintype "output"))
    )
    (net (code "79") (name "Net-(IC7-L2)") (class "Default")
      (node (ref "DIS4") (pin "12") (pinfunction "12_12") (pintype "bidirectional"))
      (node (ref "IC7") (pin "18") (pinfunction "L2_18") (pintype "output"))
    )
    (net (code "80") (name "Net-(IC7-L3)") (class "Default")
      (node (ref "DIS4") (pin "13") (pinfunction "13_13") (pintype "bidirectional"))
      (node (ref "IC7") (pin "17") (pinfunction "L3_17") (pintype "output"))
    )
    (net (code "81") (name "Net-(IC7-L4)") (class "Default")
      (node (ref "DIS4") (pin "14") (pinfunction "14_14") (pintype "bidirectional"))
      (node (ref "IC7") (pin "16") (pinfunction "L4_16") (pintype "output"))
    )
    (net (code "82") (name "Net-(IC7-L5)") (class "Default")
      (node (ref "DIS4") (pin "15") (pinfunction "15_15") (pintype "bidirectional"))
      (node (ref "IC7") (pin "15") (pinfunction "L5_15") (pintype "output"))
    )
    (net (code "83") (name "Net-(IC7-L6)") (class "Default")
      (node (ref "DIS4") (pin "16") (pinfunction "16_16") (pintype "bidirectional"))
      (node (ref "IC7") (pin "14") (pinfunction "L6_14") (pintype "output"))
    )
    (net (code "84") (name "Net-(IC7-L7)") (class "Default")
      (node (ref "DIS4") (pin "17") (pinfunction "17_17") (pintype "bidirectional"))
      (node (ref "IC7") (pin "13") (pinfunction "L7_13") (pintype "output"))
    )
    (net (code "85") (name "Net-(IC7-L8)") (class "Default")
      (node (ref "DIS4") (pin "18") (pinfunction "18_18") (pintype "bidirectional"))
      (node (ref "IC7") (pin "12") (pinfunction "L8_12") (pintype "output"))
    )
    (net (code "86") (name "Net-(IC7-L9)") (class "Default")
      (node (ref "DIS4") (pin "19") (pinfunction "19_19") (pintype "bidirectional"))
      (node (ref "IC7") (pin "11") (pinfunction "L9_11") (pintype "output"))
    )
    (net (code "87") (name "Net-(IC7-L10)") (class "Default")
      (node (ref "DIS4") (pin "20") (pinfunction "20_20") (pintype "bidirectional"))
      (node (ref "IC7") (pin "10") (pinfunction "L10_10") (pintype "output"))
    )
    (net (code "88") (name "Net-(IC7-RHI)") (class "Default")
      (node (ref "IC7") (pin "6") (pinfunction "RHI_6") (pintype "input"))
      (node (ref "IC7") (pin "7") (pinfunction "VR_7") (pintype "output"))
      (node (ref "R49") (pin "2") (pinfunction "2_2") (pintype "passive"))
    )
    (net (code "89") (name "Net-(IC8-ADJ)") (class "Default")
      (node (ref "IC8") (pin "8") (pinfunction "ADJ_8") (pintype "input"))
      (node (ref "R51") (pin "1") (pinfunction "1_1") (pintype "passive"))
      (node (ref "R52") (pin "2") (pinfunction "2_2") (pintype "passive"))
    )
    (net (code "90") (name "Net-(IC8-L1)") (class "Default")
      (node (ref "DIS5") (pin "11") (pinfunction "11_11") (pintype "bidirectional"))
      (node (ref "IC8") (pin "1") (pinfunction "L1_1") (pintype "output"))
    )
    (net (code "91") (name "Net-(IC8-L2)") (class "Default")
      (node (ref "DIS5") (pin "12") (pinfunction "12_12") (pintype "bidirectional"))
      (node (ref "IC8") (pin "18") (pinfunction "L2_18") (pintype "output"))
    )
    (net (code "92") (name "Net-(IC8-L3)") (class "Default")
      (node (ref "DIS5") (pin "13") (pinfunction "13_13") (pintype "bidirectional"))
      (node (ref "IC8") (pin "17") (pinfunction "L3_17") (pintype "output"))
    )
    (net (code "93") (name "Net-(IC8-L4)") (class "Default")
      (node (ref "DIS5") (pin "14") (pinfunction "14_14") (pintype "bidirectional"))
      (node (ref "IC8") (pin "16") (pinfunction "L4_16") (pintype "output"))
    )
    (net (code "94") (name "Net-(IC8-L5)") (class "Default")
      (node (ref "DIS5") (pin "15") (pinfunction "15_15") (pintype "bidirectional"))
      (node (ref "IC8") (pin "15") (pinfunction "L5_15") (pintype "output"))
    )
    (net (code "95") (name "Net-(IC8-L6)") (class "Default")
      (node (ref "DIS5") (pin "16") (pinfunction "16_16") (pintype "bidirectional"))
      (node (ref "IC8") (pin "14") (pinfunction "L6_14") (pintype "output"))
    )
    (net (code "96") (name "Net-(IC8-L7)") (class "Default")
      (node (ref "DIS5") (pin "17") (pinfunction "17_17") (pintype "bidirectional"))
      (node (ref "IC8") (pin "13") (pinfunction "L7_13") (pintype "output"))
    )
    (net (code "97") (name "Net-(IC8-L8)") (class "Default")
      (node (ref "DIS5") (pin "18") (pinfunction "18_18") (pintype "bidirectional"))
      (node (ref "IC8") (pin "12") (pinfunction "L8_12") (pintype "output"))
    )
    (net (code "98") (name "Net-(IC8-L9)") (class "Default")
      (node (ref "DIS5") (pin "19") (pinfunction "19_19") (pintype "bidirectional"))
      (node (ref "IC8") (pin "11") (pinfunction "L9_11") (pintype "output"))
    )
    (net (code "99") (name "Net-(IC8-L10)") (class "Default")
      (node (ref "DIS5") (pin "20") (pinfunction "20_20") (pintype "bidirectional"))
      (node (ref "IC8") (pin "10") (pinfunction "L10_10") (pintype "output"))
    )
    (net (code "100") (name "Net-(IC8-RHI)") (class "Default")
      (node (ref "IC8") (pin "6") (pinfunction "RHI_6") (pintype "input"))
      (node (ref "IC8") (pin "7") (pinfunction "VR_7") (pintype "output"))
      (node (ref "R51") (pin "2") (pinfunction "2_2") (pintype "passive"))
    )
    (net (code "101") (name "Net-(IC9-ADJ)") (class "Default")
      (node (ref "IC9") (pin "8") (pinfunction "ADJ_8") (pintype "input"))
      (node (ref "R53") (pin "1") (pinfunction "1_1") (pintype "passive"))
      (node (ref "R54") (pin "2") (pinfunction "2_2") (pintype "passive"))
    )
    (net (code "102") (name "Net-(IC9-L1)") (class "Default")
      (node (ref "DIS6") (pin "11") (pinfunction "11_11") (pintype "bidirectional"))
      (node (ref "IC9") (pin "1") (pinfunction "L1_1") (pintype "output"))
    )
    (net (code "103") (name "Net-(IC9-L2)") (class "Default")
      (node (ref "DIS6") (pin "12") (pinfunction "12_12") (pintype "bidirectional"))
      (node (ref "IC9") (pin "18") (pinfunction "L2_18") (pintype "output"))
    )
    (net (code "104") (name "Net-(IC9-L3)") (class "Default")
      (node (ref "DIS6") (pin "13") (pinfunction "13_13") (pintype "bidirectional"))
      (node (ref "IC9") (pin "17") (pinfunction "L3_17") (pintype "output"))
    )
    (net (code "105") (name "Net-(IC9-L4)") (class "Default")
      (node (ref "DIS6") (pin "14") (pinfunction "14_14") (pintype "bidirectional"))
      (node (ref "IC9") (pin "16") (pinfunction "L4_16") (pintype "output"))
    )
    (net (code "106") (name "Net-(IC9-L5)") (class "Default")
      (node (ref "DIS6") (pin "15") (pinfunction "15_15") (pintype "bidirectional"))
      (node (ref "IC9") (pin "15") (pinfunction "L5_15") (pintype "output"))
    )
    (net (code "107") (name "Net-(IC9-L6)") (class "Default")
      (node (ref "DIS6") (pin "16") (pinfunction "16_16") (pintype "bidirectional"))
      (node (ref "IC9") (pin "14") (pinfunction "L6_14") (pintype "output"))
    )
    (net (code "108") (name "Net-(IC9-L7)") (class "Default")
      (node (ref "DIS6") (pin "17") (pinfunction "17_17") (pintype "bidirectional"))
      (node (ref "IC9") (pin "13") (pinfunction "L7_13") (pintype "output"))
    )
    (net (code "109") (name "Net-(IC9-L8)") (class "Default")
      (node (ref "DIS6") (pin "18") (pinfunction "18_18") (pintype "bidirectional"))
      (node (ref "IC9") (pin "12") (pinfunction "L8_12") (pintype "output"))
    )
    (net (code "110") (name "Net-(IC9-L9)") (class "Default")
      (node (ref "DIS6") (pin "19") (pinfunction "19_19") (pintype "bidirectional"))
      (node (ref "IC9") (pin "11") (pinfunction "L9_11") (pintype "output"))
    )
    (net (code "111") (name "Net-(IC9-L10)") (class "Default")
      (node (ref "DIS6") (pin "20") (pinfunction "20_20") (pintype "bidirectional"))
      (node (ref "IC9") (pin "10") (pinfunction "L10_10") (pintype "output"))
    )
    (net (code "112") (name "Net-(IC9-RHI)") (class "Default")
      (node (ref "IC9") (pin "6") (pinfunction "RHI_6") (pintype "input"))
      (node (ref "IC9") (pin "7") (pinfunction "VR_7") (pintype "output"))
      (node (ref "R53") (pin "2") (pinfunction "2_2") (pintype "passive"))
    )
    (net (code "113") (name "Net-(IC10-ADJ)") (class "Default")
      (node (ref "IC10") (pin "8") (pinfunction "ADJ_8") (pintype "input"))
      (node (ref "R55") (pin "1") (pinfunction "1_1") (pintype "passive"))
      (node (ref "R56") (pin "2") (pinfunction "2_2") (pintype "passive"))
    )
    (net (code "114") (name "Net-(IC10-L1)") (class "Default")
      (node (ref "DIS7") (pin "11") (pinfunction "11_11") (pintype "bidirectional"))
      (node (ref "IC10") (pin "1") (pinfunction "L1_1") (pintype "output"))
    )
    (net (code "115") (name "Net-(IC10-L2)") (class "Default")
      (node (ref "DIS7") (pin "12") (pinfunction "12_12") (pintype "bidirectional"))
      (node (ref "IC10") (pin "18") (pinfunction "L2_18") (pintype "output"))
    )
    (net (code "116") (name "Net-(IC10-L3)") (class "Default")
      (node (ref "DIS7") (pin "13") (pinfunction "13_13") (pintype "bidirectional"))
      (node (ref "IC10") (pin "17") (pinfunction "L3_17") (pintype "output"))
    )
    (net (code "117") (name "Net-(IC10-L4)") (class "Default")
      (node (ref "DIS7") (pin "14") (pinfunction "14_14") (pintype "bidirectional"))
      (node (ref "IC10") (pin "16") (pinfunction "L4_16") (pintype "output"))
    )
    (net (code "118") (name "Net-(IC10-L5)") (class "Default")
      (node (ref "DIS7") (pin "15") (pinfunction "15_15") (pintype "bidirectional"))
      (node (ref "IC10") (pin "15") (pinfunction "L5_15") (pintype "output"))
    )
    (net (code "119") (name "Net-(IC10-L6)") (class "Default")
      (node (ref "DIS7") (pin "16") (pinfunction "16_16") (pintype "bidirectional"))
      (node (ref "IC10") (pin "14") (pinfunction "L6_14") (pintype "output"))
    )
    (net (code "120") (name "Net-(IC10-L7)") (class "Default")
      (node (ref "DIS7") (pin "17") (pinfunction "17_17") (pintype "bidirectional"))
      (node (ref "IC10") (pin "13") (pinfunction "L7_13") (pintype "output"))
    )
    (net (code "121") (name "Net-(IC10-L8)") (class "Default")
      (node (ref "DIS7") (pin "18") (pinfunction "18_18") (pintype "bidirectional"))
      (node (ref "IC10") (pin "12") (pinfunction "L8_12") (pintype "output"))
    )
    (net (code "122") (name "Net-(IC10-L9)") (class "Default")
      (node (ref "DIS7") (pin "19") (pinfunction "19_19") (pintype "bidirectional"))
      (node (ref "IC10") (pin "11") (pinfunction "L9_11") (pintype "output"))
    )
    (net (code "123") (name "Net-(IC10-L10)") (class "Default")
      (node (ref "DIS7") (pin "20") (pinfunction "20_20") (pintype "bidirectional"))
      (node (ref "IC10") (pin "10") (pinfunction "L10_10") (pintype "output"))
    )
    (net (code "124") (name "Net-(IC10-RHI)") (class "Default")
      (node (ref "IC10") (pin "6") (pinfunction "RHI_6") (pintype "input"))
      (node (ref "IC10") (pin "7") (pinfunction "VR_7") (pintype "output"))
      (node (ref "R55") (pin "2") (pinfunction "2_2") (pintype "passive"))
    )
    (net (code "125") (name "Net-(IC11-ADJ)") (class "Default")
      (node (ref "IC11") (pin "8") (pinfunction "ADJ_8") (pintype "input"))
      (node (ref "R57") (pin "1") (pinfunction "1_1") (pintype "passive"))
      (node (ref "R58") (pin "2") (pinfunction "2_2") (pintype "passive"))
    )
    (net (code "126") (name "Net-(IC11-L1)") (class "Default")
      (node (ref "DIS8") (pin "11") (pinfunction "11_11") (pintype "bidirectional"))
      (node (ref "IC11") (pin "1") (pinfunction "L1_1") (pintype "output"))
    )
    (net (code "127") (name "Net-(IC11-L2)") (class "Default")
      (node (ref "DIS8") (pin "12") (pinfunction "12_12") (pintype "bidirectional"))
      (node (ref "IC11") (pin "18") (pinfunction "L2_18") (pintype "output"))
    )
    (net (code "128") (name "Net-(IC11-L3)") (class "Default")
      (node (ref "DIS8") (pin "13") (pinfunction "13_13") (pintype "bidirectional"))
      (node (ref "IC11") (pin "17") (pinfunction "L3_17") (pintype "output"))
    )
    (net (code "129") (name "Net-(IC11-L4)") (class "Default")
      (node (ref "DIS8") (pin "14") (pinfunction "14_14") (pintype "bidirectional"))
      (node (ref "IC11") (pin "16") (pinfunction "L4_16") (pintype "output"))
    )
    (net (code "130") (name "Net-(IC11-L5)") (class "Default")
      (node (ref "DIS8") (pin "15") (pinfunction "15_15") (pintype "bidirectional"))
      (node (ref "IC11") (pin "15") (pinfunction "L5_15") (pintype "output"))
    )
    (net (code "131") (name "Net-(IC11-L6)") (class "Default")
      (node (ref "DIS8") (pin "16") (pinfunction "16_16") (pintype "bidirectional"))
      (node (ref "IC11") (pin "14") (pinfunction "L6_14") (pintype "output"))
    )
    (net (code "132") (name "Net-(IC11-L7)") (class "Default")
      (node (ref "DIS8") (pin "17") (pinfunction "17_17") (pintype "bidirectional"))
      (node (ref "IC11") (pin "13") (pinfunction "L7_13") (pintype "output"))
    )
    (net (code "133") (name "Net-(IC11-L8)") (class "Default")
      (node (ref "DIS8") (pin "18") (pinfunction "18_18") (pintype "bidirectional"))
      (node (ref "IC11") (pin "12") (pinfunction "L8_12") (pintype "output"))
    )
    (net (code "134") (name "Net-(IC11-L9)") (class "Default")
      (node (ref "DIS8") (pin "19") (pinfunction "19_19") (pintype "bidirectional"))
      (node (ref "IC11") (pin "11") (pinfunction "L9_11") (pintype "output"))
    )
    (net (code "135") (name "Net-(IC11-L10)") (class "Default")
      (node (ref "DIS8") (pin "20") (pinfunction "20_20") (pintype "bidirectional"))
      (node (ref "IC11") (pin "10") (pinfunction "L10_10") (pintype "output"))
    )
    (net (code "136") (name "Net-(IC11-RHI)") (class "Default")
      (node (ref "IC11") (pin "6") (pinfunction "RHI_6") (pintype "input"))
      (node (ref "IC11") (pin "7") (pinfunction "VR_7") (pintype "output"))
      (node (ref "R57") (pin "2") (pinfunction "2_2") (pintype "passive"))
    )
    (net (code "137") (name "Net-(IC12-ADJ)") (class "Default")
      (node (ref "IC12") (pin "8") (pinfunction "ADJ_8") (pintype "input"))
      (node (ref "R59") (pin "1") (pinfunction "1_1") (pintype "passive"))
      (node (ref "R60") (pin "2") (pinfunction "2_2") (pintype "passive"))
    )
    (net (code "138") (name "Net-(IC12-L1)") (class "Default")
      (node (ref "DIS9") (pin "11") (pinfunction "11_11") (pintype "bidirectional"))
      (node (ref "IC12") (pin "1") (pinfunction "L1_1") (pintype "output"))
    )
    (net (code "139") (name "Net-(IC12-L2)") (class "Default")
      (node (ref "DIS9") (pin "12") (pinfunction "12_12") (pintype "bidirectional"))
      (node (ref "IC12") (pin "18") (pinfunction "L2_18") (pintype "output"))
    )
    (net (code "140") (name "Net-(IC12-L3)") (class "Default")
      (node (ref "DIS9") (pin "13") (pinfunction "13_13") (pintype "bidirectional"))
      (node (ref "IC12") (pin "17") (pinfunction "L3_17") (pintype "output"))
    )
    (net (code "141") (name "Net-(IC12-L4)") (class "Default")
      (node (ref "DIS9") (pin "14") (pinfunction "14_14") (pintype "bidirectional"))
      (node (ref "IC12") (pin "16") (pinfunction "L4_16") (pintype "output"))
    )
    (net (code "142") (name "Net-(IC12-L5)") (class "Default")
      (node (ref "DIS9") (pin "15") (pinfunction "15_15") (pintype "bidirectional"))
      (node (ref "IC12") (pin "15") (pinfunction "L5_15") (pintype "output"))
    )
    (net (code "143") (name "Net-(IC12-L6)") (class "Default")
      (node (ref "DIS9") (pin "16") (pinfunction "16_16") (pintype "bidirectional"))
      (node (ref "IC12") (pin "14") (pinfunction "L6_14") (pintype "output"))
    )
    (net (code "144") (name "Net-(IC12-L7)") (class "Default")
      (node (ref "DIS9") (pin "17") (pinfunction "17_17") (pintype "bidirectional"))
      (node (ref "IC12") (pin "13") (pinfunction "L7_13") (pintype "output"))
    )
    (net (code "145") (name "Net-(IC12-L8)") (class "Default")
      (node (ref "DIS9") (pin "18") (pinfunction "18_18") (pintype "bidirectional"))
      (node (ref "IC12") (pin "12") (pinfunction "L8_12") (pintype "output"))
    )
    (net (code "146") (name "Net-(IC12-L9)") (class "Default")
      (node (ref "DIS9") (pin "19") (pinfunction "19_19") (pintype "bidirectional"))
      (node (ref "IC12") (pin "11") (pinfunction "L9_11") (pintype "output"))
    )
    (net (code "147") (name "Net-(IC12-L10)") (class "Default")
      (node (ref "DIS9") (pin "20") (pinfunction "20_20") (pintype "bidirectional"))
      (node (ref "IC12") (pin "10") (pinfunction "L10_10") (pintype "output"))
    )
    (net (code "148") (name "Net-(IC12-RHI)") (class "Default")
      (node (ref "IC12") (pin "6") (pinfunction "RHI_6") (pintype "input"))
      (node (ref "IC12") (pin "7") (pinfunction "VR_7") (pintype "output"))
      (node (ref "R59") (pin "2") (pinfunction "2_2") (pintype "passive"))
    )
    (net (code "149") (name "Net-(IC13-ADJ)") (class "Default")
      (node (ref "IC13") (pin "8") (pinfunction "ADJ_8") (pintype "input"))
      (node (ref "R61") (pin "1") (pinfunction "1_1") (pintype "passive"))
      (node (ref "R62") (pin "2") (pinfunction "2_2") (pintype "passive"))
    )
    (net (code "150") (name "Net-(IC13-L1)") (class "Default")
      (node (ref "DIS10") (pin "11") (pinfunction "11_11") (pintype "bidirectional"))
      (node (ref "IC13") (pin "1") (pinfunction "L1_1") (pintype "output"))
    )
    (net (code "151") (name "Net-(IC13-L2)") (class "Default")
      (node (ref "DIS10") (pin "12") (pinfunction "12_12") (pintype "bidirectional"))
      (node (ref "IC13") (pin "18") (pinfunction "L2_18") (pintype "output"))
    )
    (net (code "152") (name "Net-(IC13-L3)") (class "Default")
      (node (ref "DIS10") (pin "13") (pinfunction "13_13") (pintype "bidirectional"))
      (node (ref "IC13") (pin "17") (pinfunction "L3_17") (pintype "output"))
    )
    (net (code "153") (name "Net-(IC13-L4)") (class "Default")
      (node (ref "DIS10") (pin "14") (pinfunction "14_14") (pintype "bidirectional"))
      (node (ref "IC13") (pin "16") (pinfunction "L4_16") (pintype "output"))
    )
    (net (code "154") (name "Net-(IC13-L5)") (class "Default")
      (node (ref "DIS10") (pin "15") (pinfunction "15_15") (pintype "bidirectional"))
      (node (ref "IC13") (pin "15") (pinfunction "L5_15") (pintype "output"))
    )
    (net (code "155") (name "Net-(IC13-L6)") (class "Default")
      (node (ref "DIS10") (pin "16") (pinfunction "16_16") (pintype "bidirectional"))
      (node (ref "IC13") (pin "14") (pinfunction "L6_14") (pintype "output"))
    )
    (net (code "156") (name "Net-(IC13-L7)") (class "Default")
      (node (ref "DIS10") (pin "17") (pinfunction "17_17") (pintype "bidirectional"))
      (node (ref "IC13") (pin "13") (pinfunction "L7_13") (pintype "output"))
    )
    (net (code "157") (name "Net-(IC13-L8)") (class "Default")
      (node (ref "DIS10") (pin "18") (pinfunction "18_18") (pintype "bidirectional"))
      (node (ref "IC13") (pin "12") (pinfunction "L8_12") (pintype "output"))
    )
    (net (code "158") (name "Net-(IC13-L9)") (class "Default")
      (node (ref "DIS10") (pin "19") (pinfunction "19_19") (pintype "bidirectional"))
      (node (ref "IC13") (pin "11") (pinfunction "L9_11") (pintype "output"))
    )
    (net (code "159") (name "Net-(IC13-L10)") (class "Default")
      (node (ref "DIS10") (pin "20") (pinfunction "20_20") (pintype "bidirectional"))
      (node (ref "IC13") (pin "10") (pinfunction "L10_10") (pintype "output"))
    )
    (net (code "160") (name "Net-(IC13-RHI)") (class "Default")
      (node (ref "IC13") (pin "6") (pinfunction "RHI_6") (pintype "input"))
      (node (ref "IC13") (pin "7") (pinfunction "VR_7") (pintype "output"))
      (node (ref "R61") (pin "2") (pinfunction "2_2") (pintype "passive"))
    )
    (net (code "161") (name "Net-(J1-L)") (class "Default")
      (node (ref "J1") (pin "2") (pinfunction "L_2") (pintype "bidirectional"))
      (node (ref "R3") (pin "1") (pinfunction "1_1") (pintype "passive"))
    )
    (net (code "162") (name "Net-(J1-R)") (class "Default")
      (node (ref "J1") (pin "4") (pinfunction "R_4") (pintype "bidirectional"))
      (node (ref "R2") (pin "1") (pinfunction "1_1") (pintype "passive"))
    )
    (net (code "163") (name "Net-(R10-PadS)") (class "Default")
      (node (ref "R10") (pin "S") (pinfunction "S_S") (pintype "passive"))
      (node (ref "R8") (pin "2") (pinfunction "2_2") (pintype "passive"))
    )
    (net (code "164") (name "Net-(R11-PadS)") (class "Default")
      (node (ref "R11") (pin "S") (pinfunction "S_S") (pintype "passive"))
      (node (ref "R9") (pin "2") (pinfunction "2_2") (pintype "passive"))
    )
    (net (code "165") (name "OUT1") (class "Default")
      (node (ref "C10") (pin "+") (pinfunction "+_+") (pintype "passive"))
      (node (ref "D1") (pin "C") (pinfunction "C_C") (pintype "passive"))
      (node (ref "IC4") (pin "5") (pinfunction "SIG_5") (pintype "input"))
    )
    (net (code "166") (name "OUT2") (class "Default")
      (node (ref "C11") (pin "+") (pinfunction "+_+") (pintype "passive"))
      (node (ref "D2") (pin "C") (pinfunction "C_C") (pintype "passive"))
      (node (ref "IC5") (pin "5") (pinfunction "SIG_5") (pintype "input"))
    )
    (net (code "167") (name "OUT3") (class "Default")
      (node (ref "C20") (pin "+") (pinfunction "+_+") (pintype "passive"))
      (node (ref "D3") (pin "C") (pinfunction "C_C") (pintype "passive"))
      (node (ref "IC6") (pin "5") (pinfunction "SIG_5") (pintype "input"))
    )
    (net (code "168") (name "OUT4") (class "Default")
      (node (ref "C21") (pin "+") (pinfunction "+_+") (pintype "passive"))
      (node (ref "D4") (pin "C") (pinfunction "C_C") (pintype "passive"))
      (node (ref "IC7") (pin "5") (pinfunction "SIG_5") (pintype "input"))
    )
    (net (code "169") (name "OUT5") (class "Default")
      (node (ref "C22") (pin "+") (pinfunction "+_+") (pintype "passive"))
      (node (ref "D5") (pin "C") (pinfunction "C_C") (pintype "passive"))
      (node (ref "IC8") (pin "5") (pinfunction "SIG_5") (pintype "input"))
    )
    (net (code "170") (name "OUT6") (class "Default")
      (node (ref "C23") (pin "+") (pinfunction "+_+") (pintype "passive"))
      (node (ref "D6") (pin "C") (pinfunction "C_C") (pintype "passive"))
      (node (ref "IC9") (pin "5") (pinfunction "SIG_5") (pintype "input"))
    )
    (net (code "171") (name "OUT7") (class "Default")
      (node (ref "C32") (pin "+") (pinfunction "+_+") (pintype "passive"))
      (node (ref "D8") (pin "C") (pinfunction "C_C") (pintype "passive"))
      (node (ref "IC10") (pin "5") (pinfunction "SIG_5") (pintype "input"))
    )
    (net (code "172") (name "OUT8") (class "Default")
      (node (ref "C33") (pin "+") (pinfunction "+_+") (pintype "passive"))
      (node (ref "D9") (pin "C") (pinfunction "C_C") (pintype "passive"))
      (node (ref "IC11") (pin "5") (pinfunction "SIG_5") (pintype "input"))
    )
    (net (code "173") (name "OUT9") (class "Default")
      (node (ref "C34") (pin "+") (pinfunction "+_+") (pintype "passive"))
      (node (ref "D10") (pin "C") (pinfunction "C_C") (pintype "passive"))
      (node (ref "IC12") (pin "5") (pinfunction "SIG_5") (pintype "input"))
    )
    (net (code "174") (name "OUT10") (class "Default")
      (node (ref "C35") (pin "+") (pinfunction "+_+") (pintype "passive"))
      (node (ref "D11") (pin "C") (pinfunction "C_C") (pintype "passive"))
      (node (ref "IC13") (pin "5") (pinfunction "SIG_5") (pintype "input"))
    )
    (net (code "175") (name "REF") (class "Default")
      (node (ref "D7") (pin "A") (pinfunction "A_A") (pintype "passive"))
      (node (ref "IC1") (pin "10") (pinfunction "+IN_10") (pintype "input"))
      (node (ref "IC1") (pin "12") (pinfunction "+IN_12") (pintype "input"))
      (node (ref "IC2") (pin "10") (pinfunction "+IN_10") (pintype "input"))
      (node (ref "IC2") (pin "12") (pinfunction "+IN_12") (pintype "input"))
      (node (ref "IC2") (pin "3") (pinfunction "+IN_3") (pintype "input"))
      (node (ref "IC2") (pin "5") (pinfunction "+IN_5") (pintype "input"))
      (node (ref "IC3") (pin "10") (pinfunction "+IN_10") (pintype "input"))
      (node (ref "IC3") (pin "12") (pinfunction "+IN_12") (pintype "input"))
      (node (ref "IC3") (pin "3") (pinfunction "+IN_3") (pintype "input"))
      (node (ref "IC3") (pin "5") (pinfunction "+IN_5") (pintype "input"))
      (node (ref "R16") (pin "1") (pinfunction "1_1") (pintype "passive"))
    )
    (net (code "176") (name "VER") (class "Default")
      (node (ref "C3") (pin "-") (pinfunction "-_-") (pintype "passive"))
      (node (ref "R12") (pin "1") (pinfunction "1_1") (pintype "passive"))
      (node (ref "R13") (pin "1") (pinfunction "1_1") (pintype "passive"))
      (node (ref "R19") (pin "1") (pinfunction "1_1") (pintype "passive"))
      (node (ref "R20") (pin "1") (pinfunction "1_1") (pintype "passive"))
      (node (ref "R21") (pin "1") (pinfunction "1_1") (pintype "passive"))
      (node (ref "R22") (pin "1") (pinfunction "1_1") (pintype "passive"))
      (node (ref "R31") (pin "1") (pinfunction "1_1") (pintype "passive"))
      (node (ref "R32") (pin "1") (pinfunction "1_1") (pintype "passive"))
      (node (ref "R33") (pin "1") (pinfunction "1_1") (pintype "passive"))
      (node (ref "R34") (pin "1") (pinfunction "1_1") (pintype "passive"))
      (node (ref "TP1") (pin "TP") (pinfunction "TP_TP") (pintype "input"))
    )
    (net (code "177") (name "unconnected-(J2-Pad2)") (class "Default")
      (node (ref "J2") (pin "2") (pinfunction "2_2") (pintype "passive"))
    )
    (net (code "178") (name "unconnected-(R1-PadA)") (class "Default")
      (node (ref "R1") (pin "A") (pinfunction "A_A") (pintype "passive"))
    )
    (net (code "179") (name "unconnected-(R10-PadA)") (class "Default")
      (node (ref "R10") (pin "A") (pinfunction "A_A") (pintype "passive"))
    )
    (net (code "180") (name "unconnected-(R11-PadA)") (class "Default")
      (node (ref "R11") (pin "A") (pinfunction "A_A") (pintype "passive"))
    )
  )
)
